# bioshield.net
KiCad netlist of a schematic drawn in EAGLE
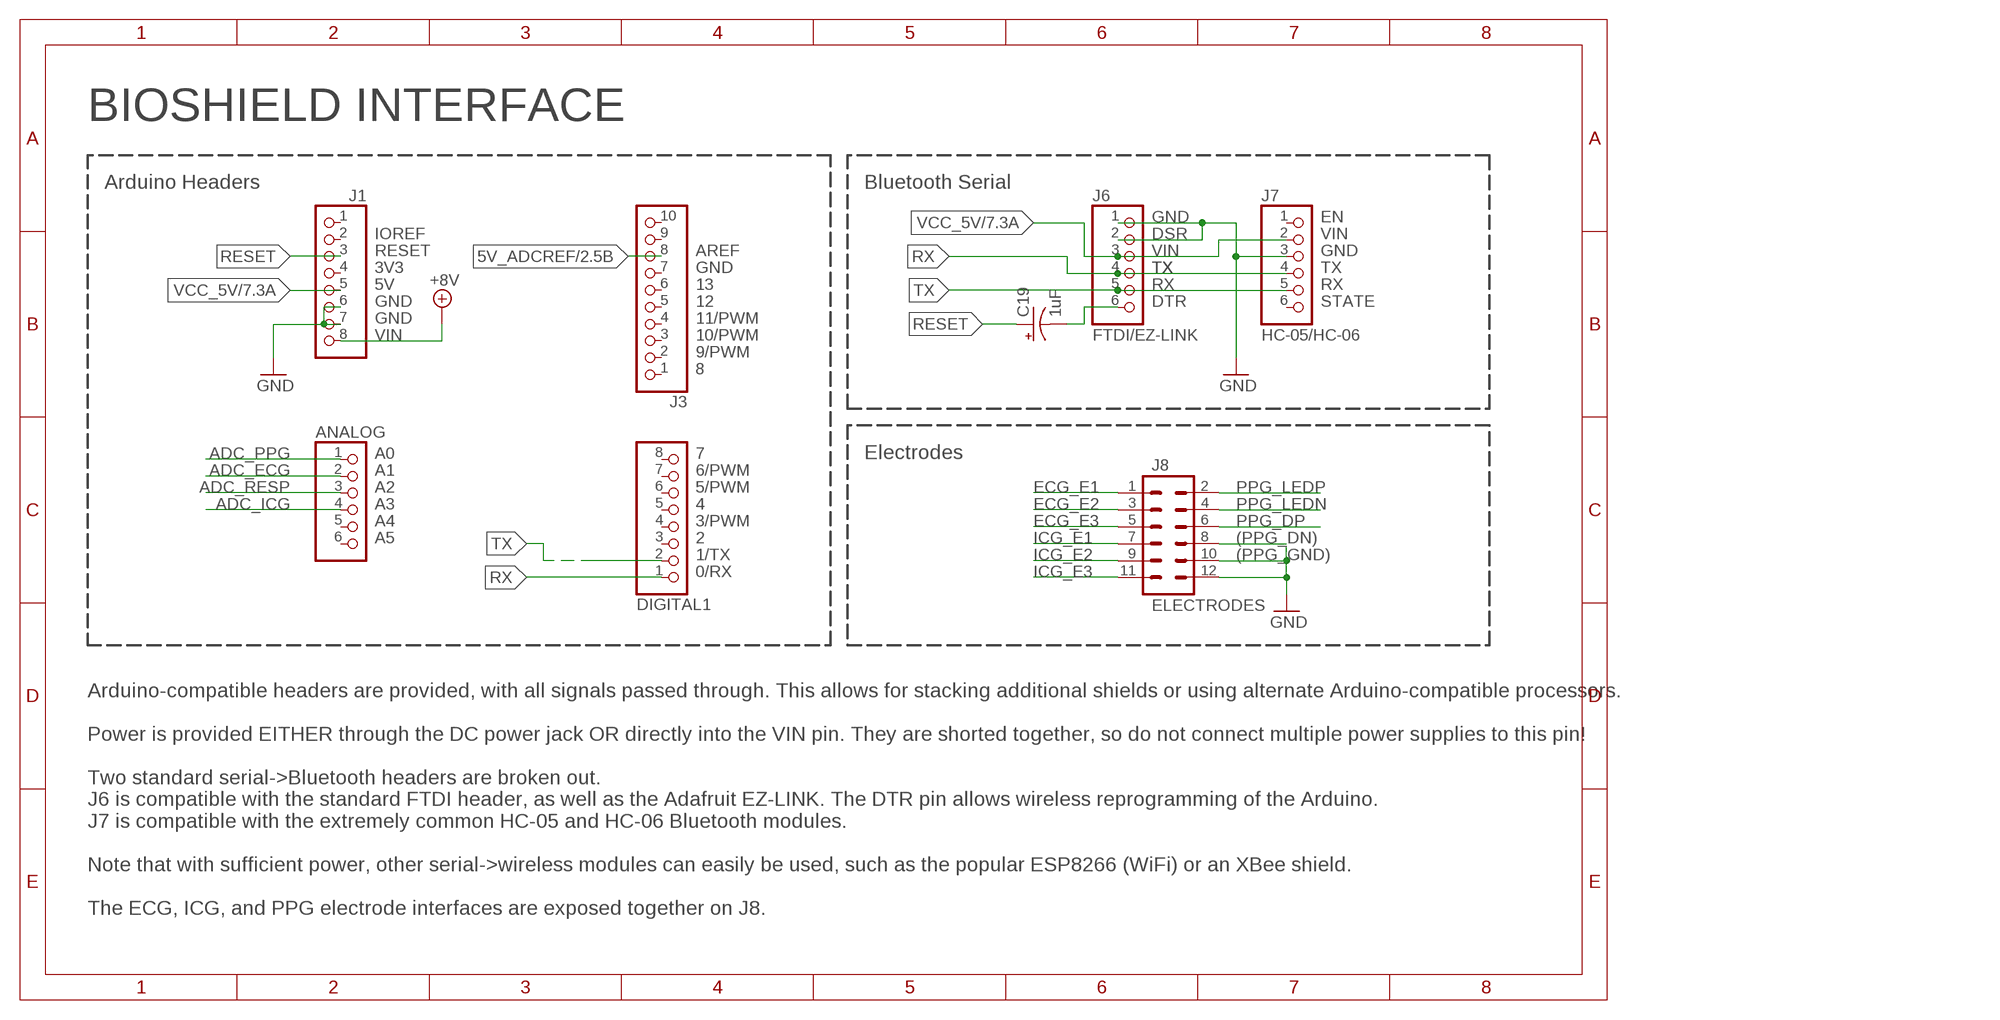
[diagram p0: schematic, sheet 1]
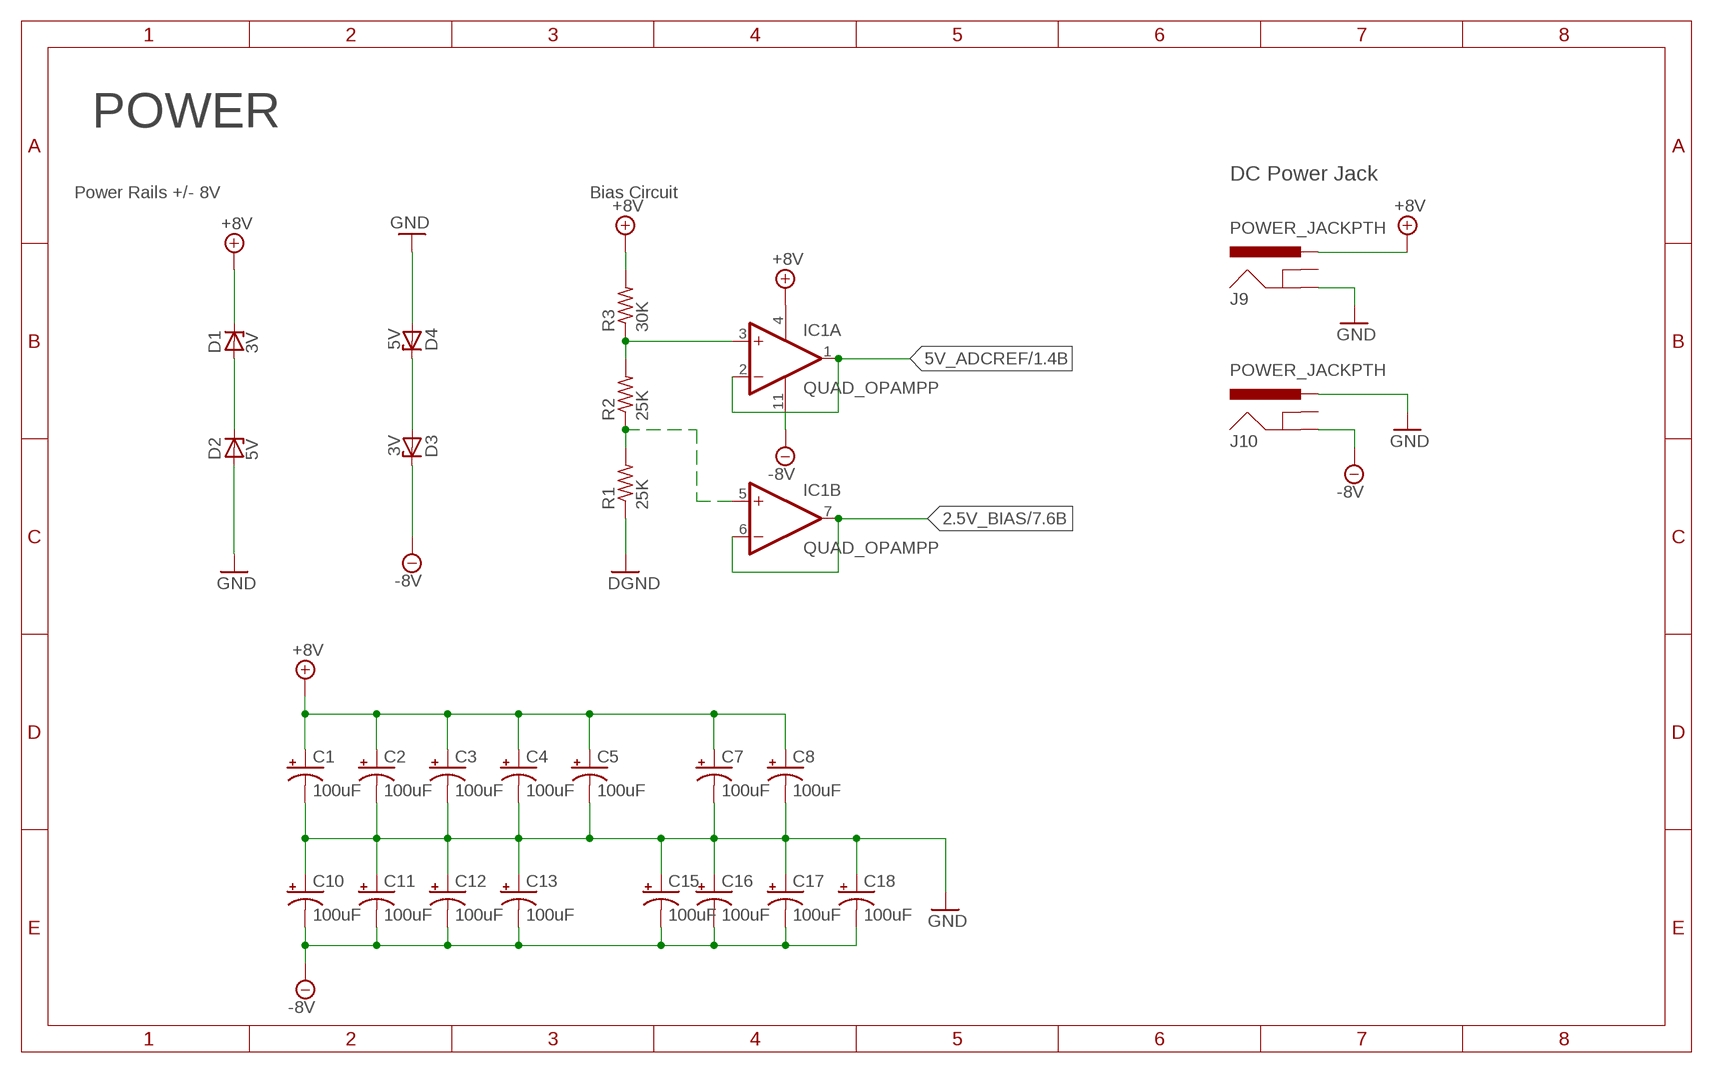
[diagram p1: schematic, sheet 2]
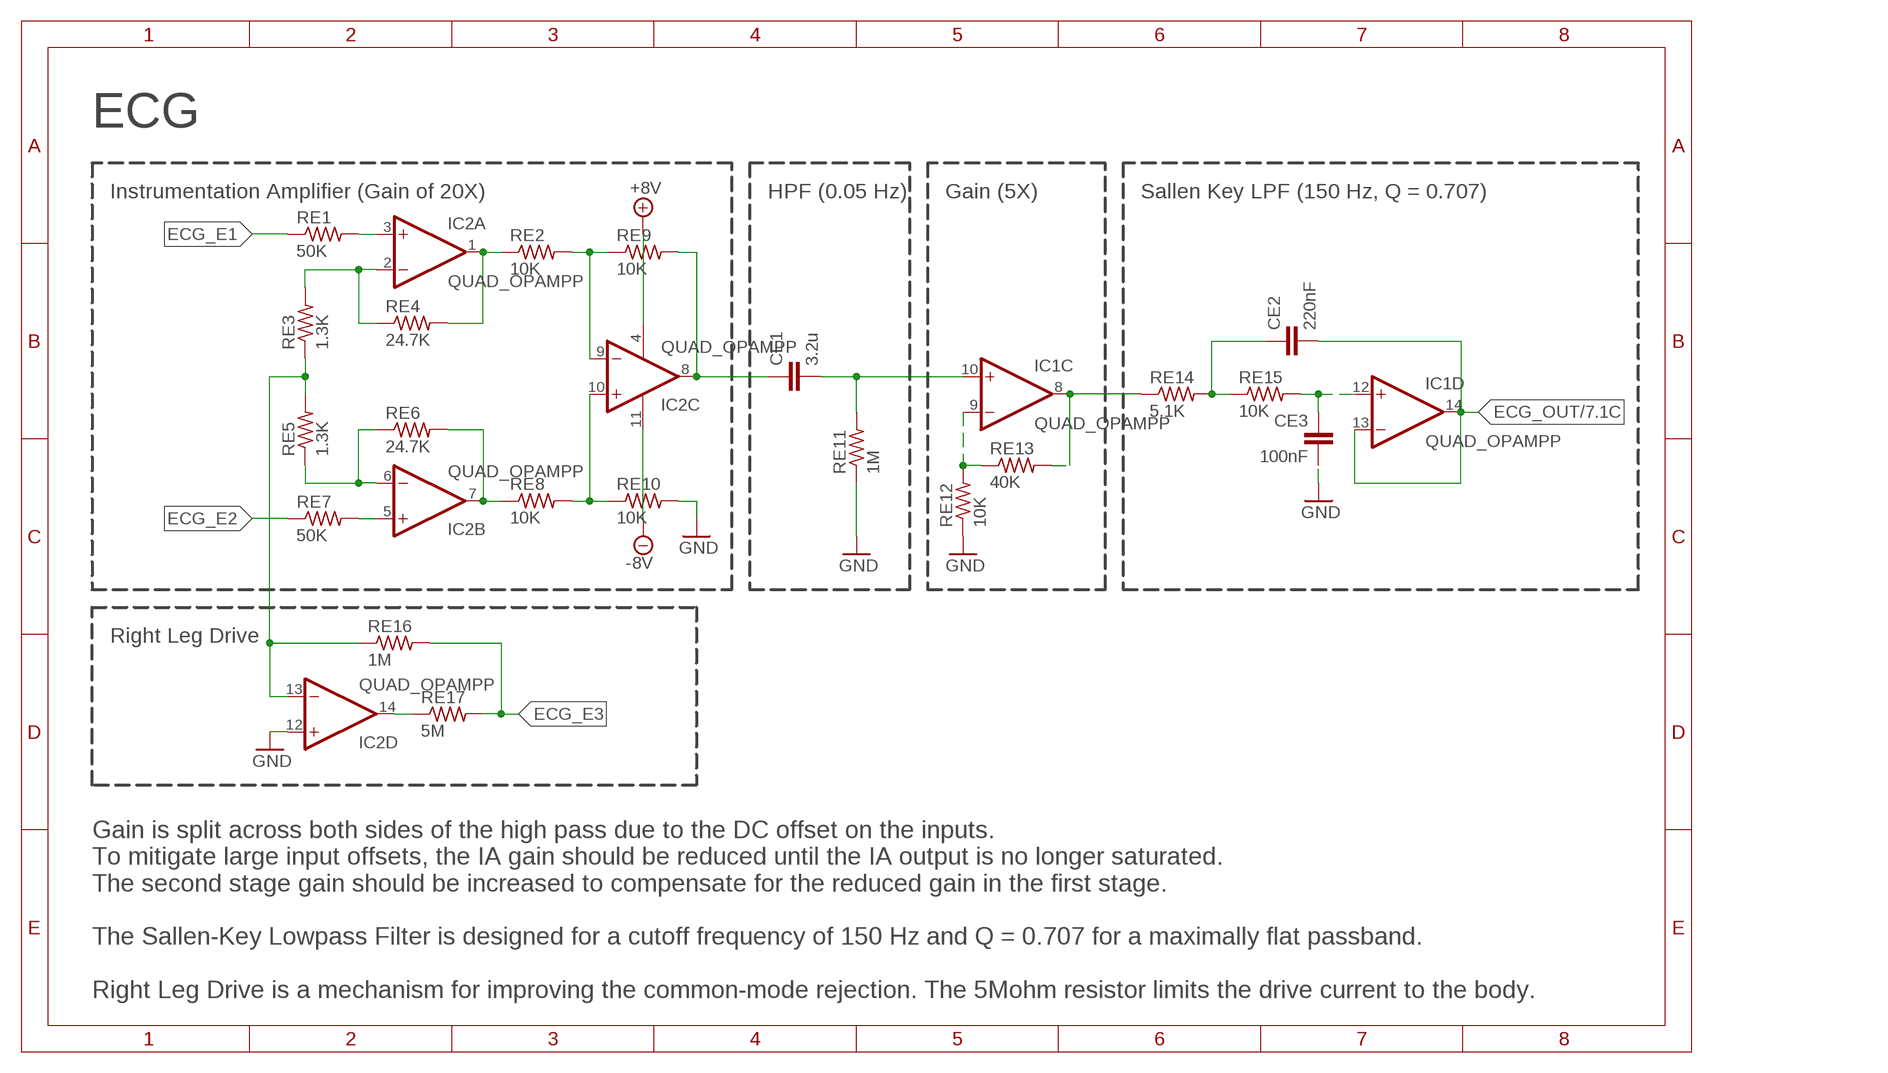
[diagram p2: schematic, sheet 3]
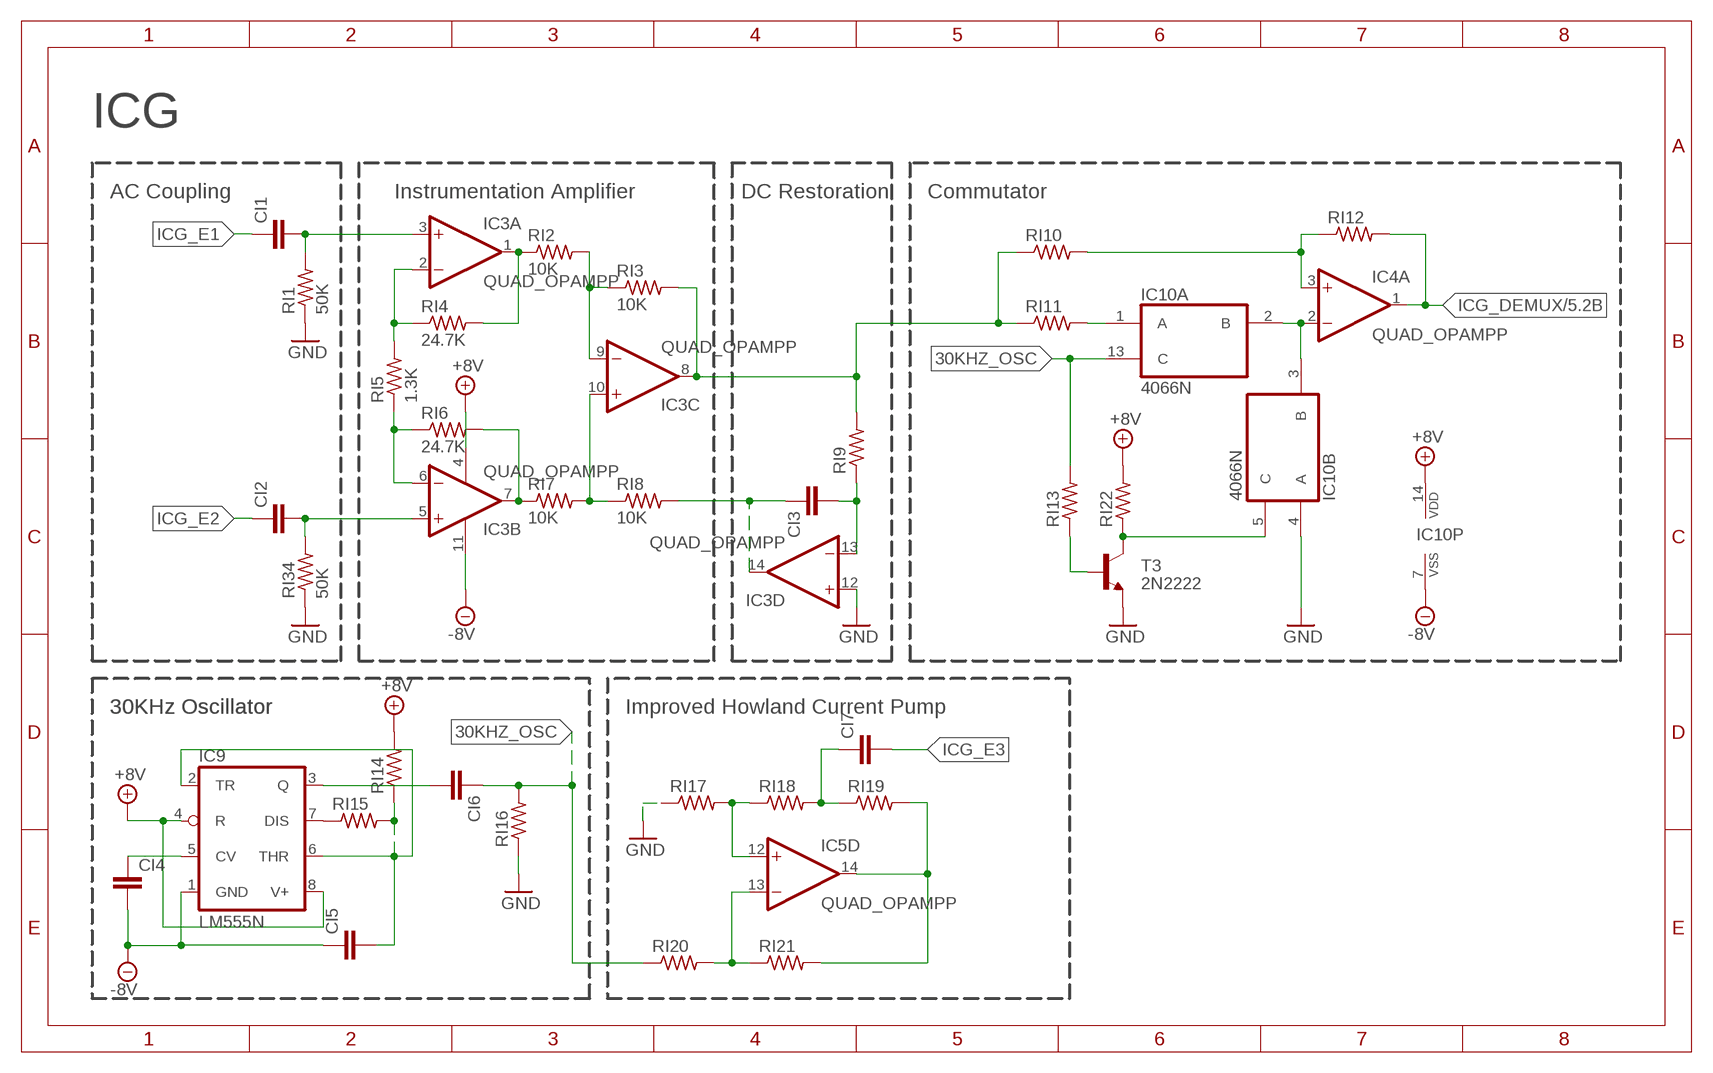
[diagram p3: schematic, sheet 4]
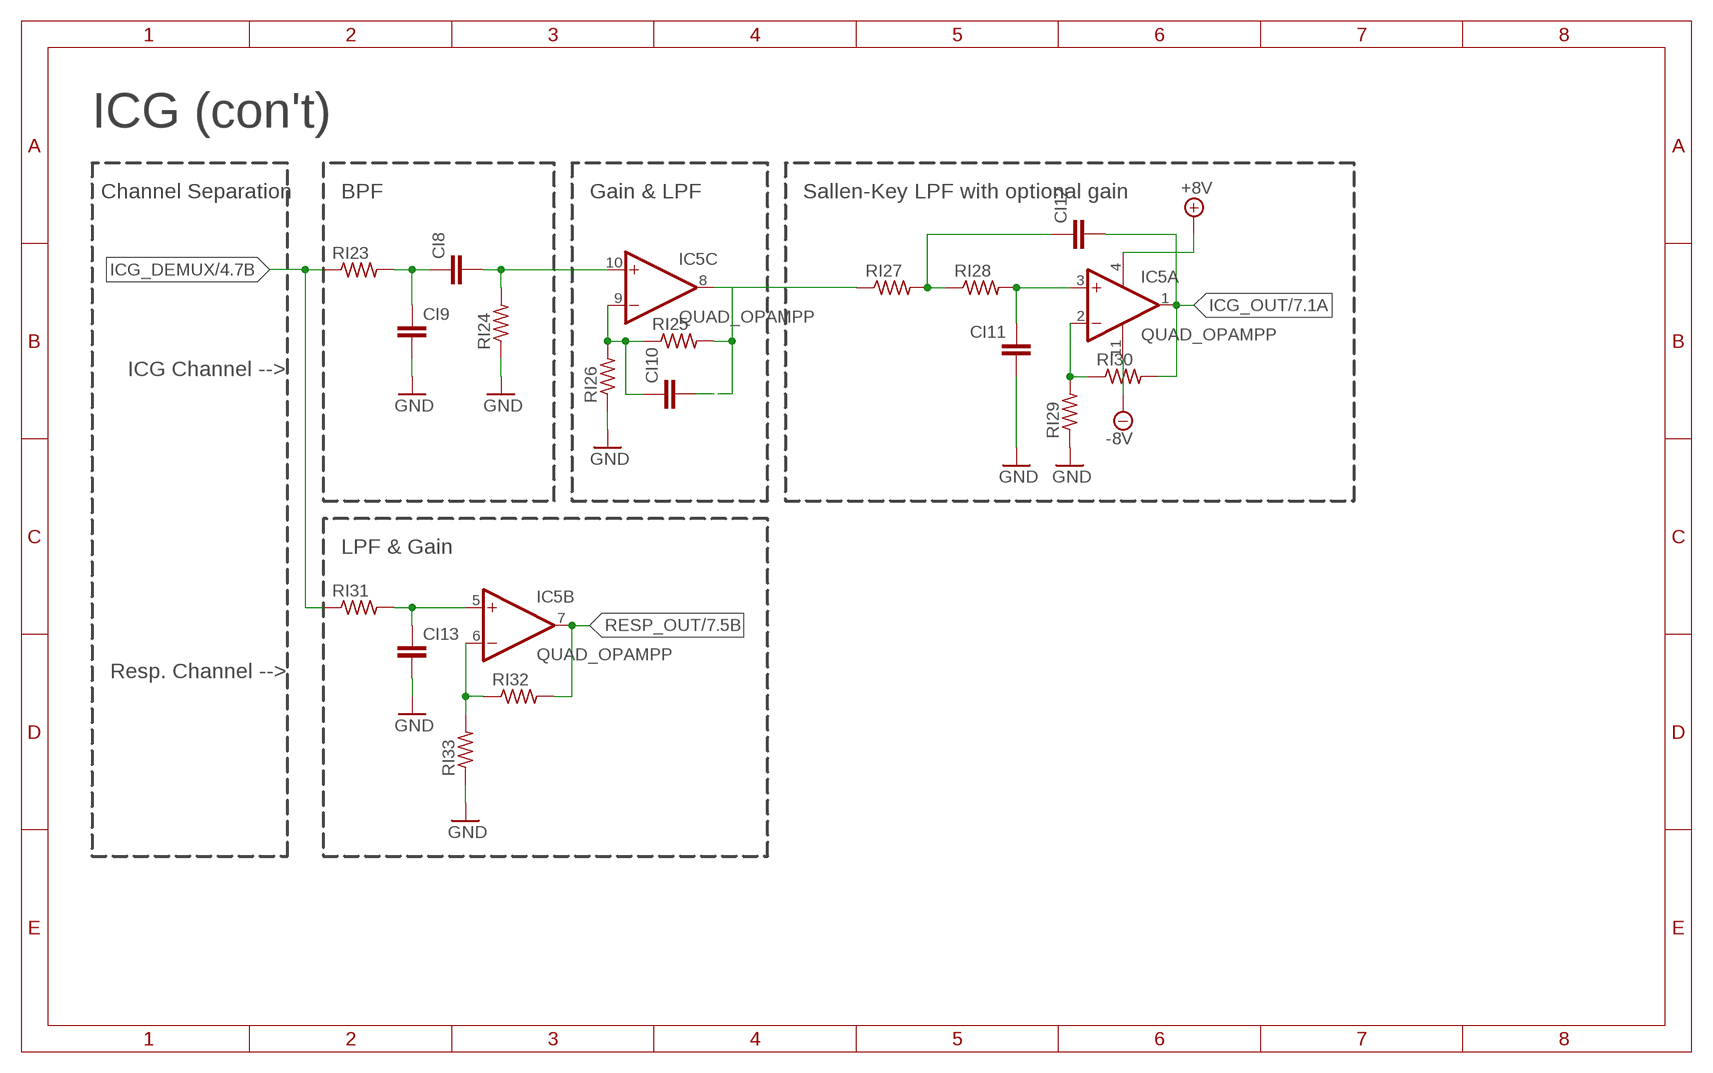
[diagram p4: schematic, sheet 5]
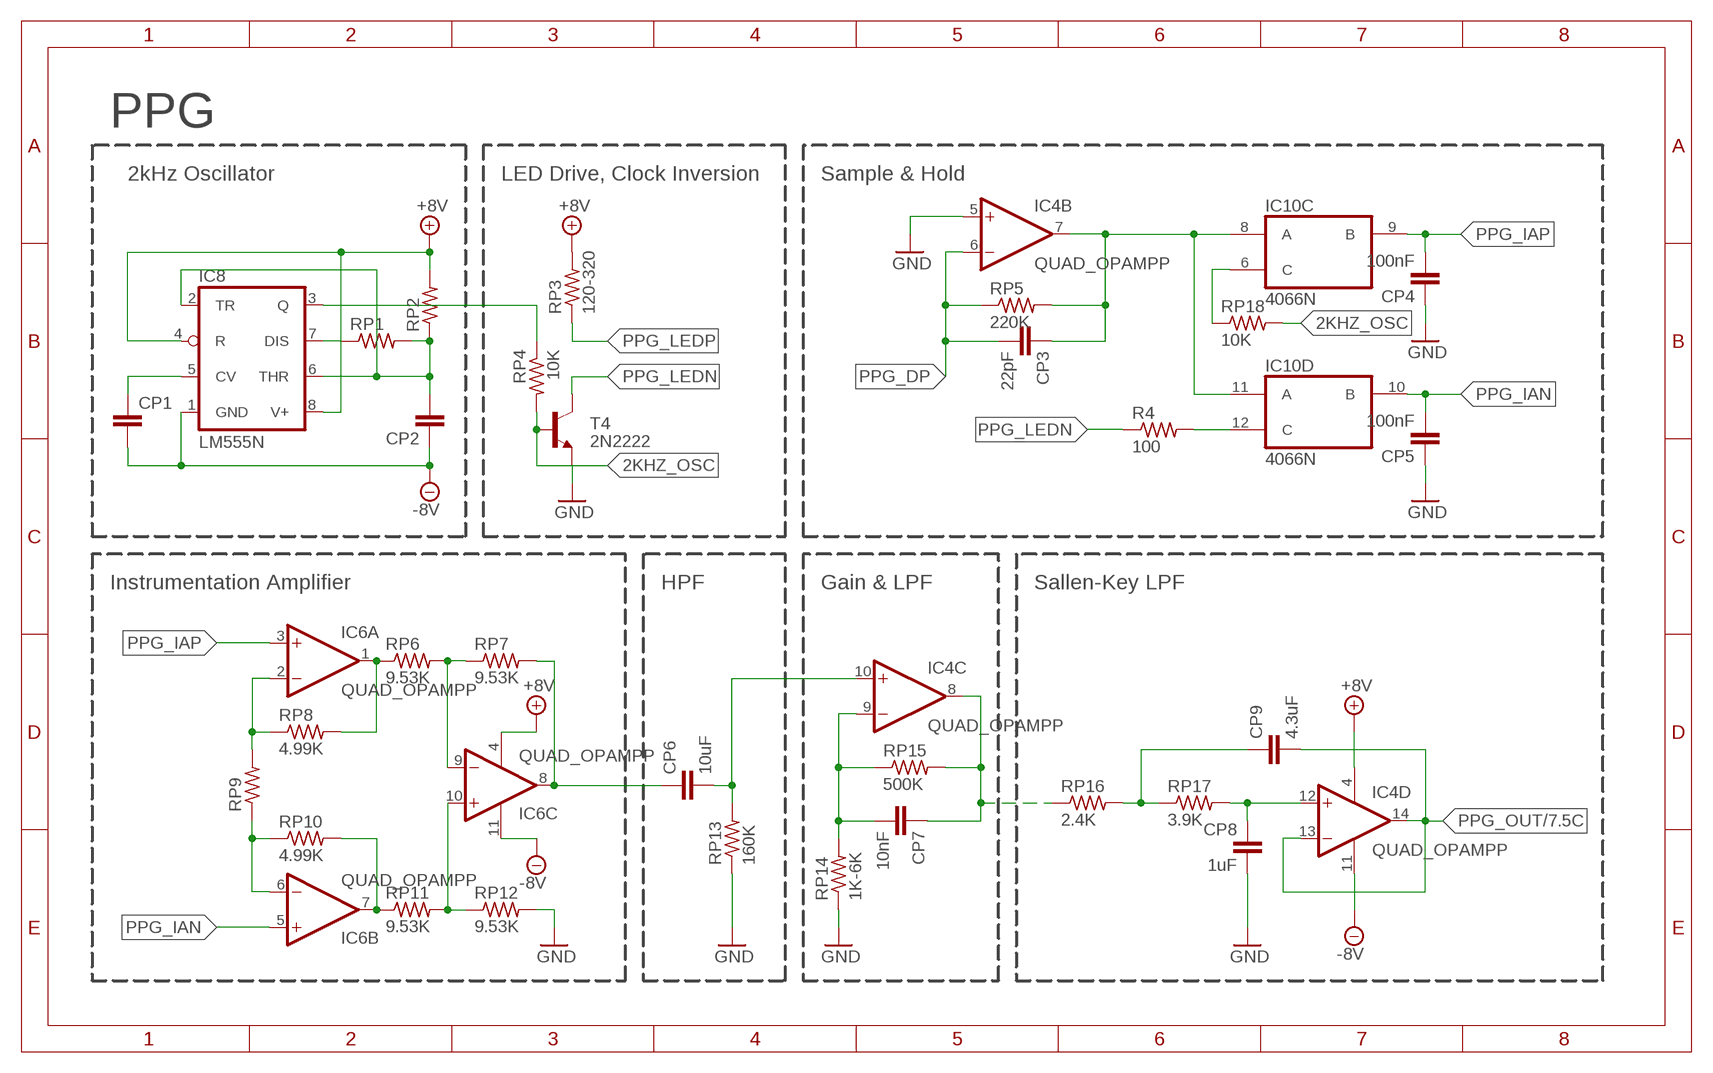
[diagram p5: schematic, sheet 6]
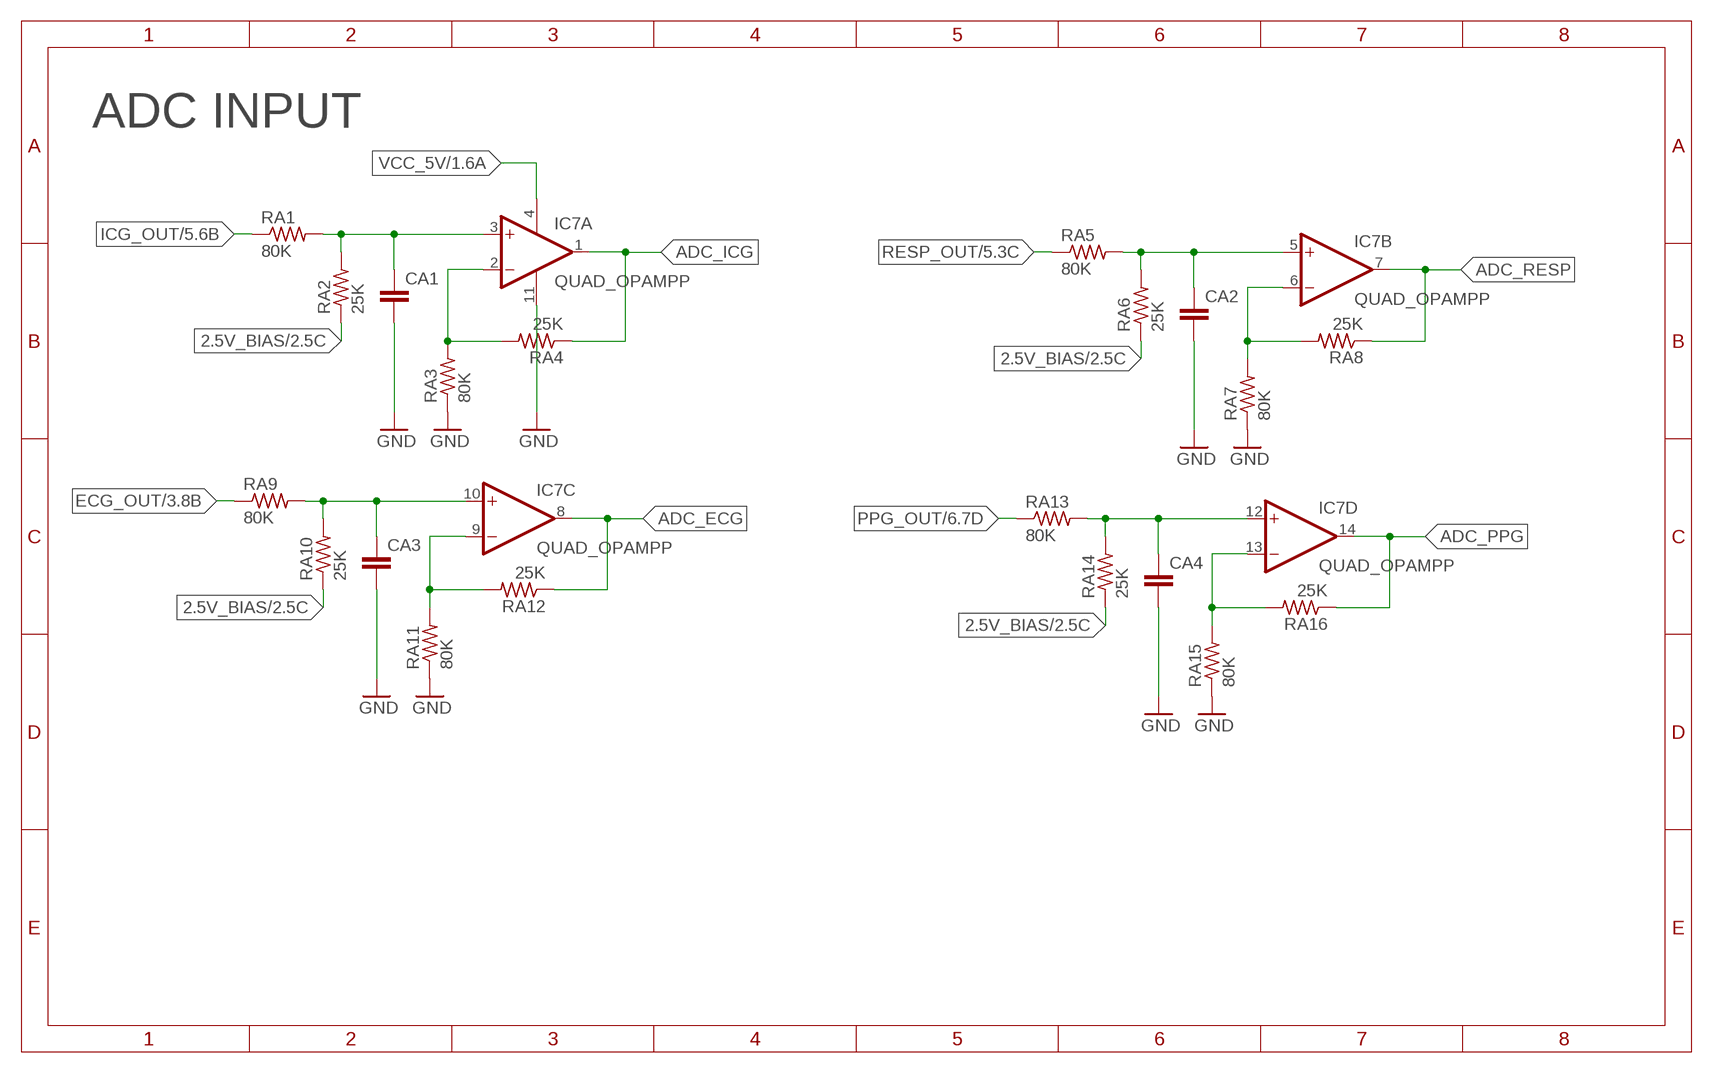
[diagram p6: schematic, sheet 7]

(export (version "E")
  (design (tool "Eeschema 10.0.6"))
  (components
    (comp (ref "CE1")
      (value "3.2u")
      (footprint "eagle-import:CAP-PTH-5MM")
      (libsource (lib "eagle-import") (part "SparkFun-Passives_CAPPTH1"))
    )
    (comp (ref "CE2")
      (value "220nF")
      (footprint "eagle-import:CAP-PTH-5MM")
      (libsource (lib "eagle-import") (part "SparkFun-Passives_CAPPTH1"))
    )
    (comp (ref "CE3")
      (value "100nF")
      (footprint "eagle-import:CAP-PTH-5MM")
      (libsource (lib "eagle-import") (part "SparkFun-Passives_CAPPTH1"))
    )
    (comp (ref "IC1")
      (value "QUAD_OPAMPP")
      (footprint "eagle-import:DIL14")
      (libsource (lib "eagle-import") (part "QUAD_OPAMPP"))
    )
    (comp (ref "IC2")
      (value "QUAD_OPAMPP")
      (footprint "eagle-import:DIL14")
      (libsource (lib "eagle-import") (part "QUAD_OPAMPP"))
    )
    (comp (ref "RE1")
      (value "50K")
      (footprint "eagle-import:0207_10")
      (libsource (lib "eagle-import") (part "R-US_0207/10"))
    )
    (comp (ref "RE2")
      (value "10K")
      (footprint "eagle-import:0207_10")
      (libsource (lib "eagle-import") (part "R-US_0207/10"))
    )
    (comp (ref "RE3")
      (value "1.3K")
      (footprint "eagle-import:0207_10")
      (libsource (lib "eagle-import") (part "R-US_0207/10"))
    )
    (comp (ref "RE4")
      (value "24.7K")
      (footprint "eagle-import:0207_10")
      (libsource (lib "eagle-import") (part "R-US_0207/10"))
    )
    (comp (ref "RE5")
      (value "1.3K")
      (footprint "eagle-import:0207_10")
      (libsource (lib "eagle-import") (part "R-US_0207/10"))
    )
    (comp (ref "RE6")
      (value "24.7K")
      (footprint "eagle-import:0207_10")
      (libsource (lib "eagle-import") (part "R-US_0207/10"))
    )
    (comp (ref "RE7")
      (value "50K")
      (footprint "eagle-import:0207_10")
      (libsource (lib "eagle-import") (part "R-US_0207/10"))
    )
    (comp (ref "RE8")
      (value "10K")
      (footprint "eagle-import:0207_10")
      (libsource (lib "eagle-import") (part "R-US_0207/10"))
    )
    (comp (ref "RE9")
      (value "10K")
      (footprint "eagle-import:0207_10")
      (libsource (lib "eagle-import") (part "R-US_0207/10"))
    )
    (comp (ref "RE10")
      (value "10K")
      (footprint "eagle-import:0207_10")
      (libsource (lib "eagle-import") (part "R-US_0207/10"))
    )
    (comp (ref "RE11")
      (value "1M")
      (footprint "eagle-import:0207_10")
      (libsource (lib "eagle-import") (part "R-US_0207/10"))
    )
    (comp (ref "RE12")
      (value "10K")
      (footprint "eagle-import:0207_10")
      (libsource (lib "eagle-import") (part "R-US_0207/10"))
    )
    (comp (ref "RE13")
      (value "40K")
      (footprint "eagle-import:0207_10")
      (libsource (lib "eagle-import") (part "R-US_0207/10"))
    )
    (comp (ref "RE14")
      (value "5.1K")
      (footprint "eagle-import:0207_10")
      (libsource (lib "eagle-import") (part "R-US_0207/10"))
    )
    (comp (ref "RE15")
      (value "10K")
      (footprint "eagle-import:0207_10")
      (libsource (lib "eagle-import") (part "R-US_0207/10"))
    )
    (comp (ref "RE16")
      (value "1M")
      (footprint "eagle-import:0207_10")
      (libsource (lib "eagle-import") (part "R-US_0207/10"))
    )
    (comp (ref "RE17")
      (value "5M")
      (footprint "eagle-import:0207_10")
      (libsource (lib "eagle-import") (part "R-US_0207/10"))
    )
    (comp (ref "CA1")
      (value "CAPPTH1")
      (footprint "eagle-import:CAP-PTH-5MM")
      (libsource (lib "eagle-import") (part "CAPPTH1"))
    )
    (comp (ref "CA2")
      (value "CAPPTH1")
      (footprint "eagle-import:CAP-PTH-5MM")
      (libsource (lib "eagle-import") (part "CAPPTH1"))
    )
    (comp (ref "CA3")
      (value "CAPPTH1")
      (footprint "eagle-import:CAP-PTH-5MM")
      (libsource (lib "eagle-import") (part "CAPPTH1"))
    )
    (comp (ref "CA4")
      (value "CAPPTH1")
      (footprint "eagle-import:CAP-PTH-5MM")
      (libsource (lib "eagle-import") (part "CAPPTH1"))
    )
    (comp (ref "IC7")
      (value "QUAD_OPAMPP")
      (footprint "eagle-import:DIL14")
      (libsource (lib "eagle-import") (part "QUAD_OPAMPP"))
    )
    (comp (ref "RA1")
      (value "80K")
      (footprint "eagle-import:0207_10")
      (libsource (lib "eagle-import") (part "R-US_0207/10"))
    )
    (comp (ref "RA2")
      (value "25K")
      (footprint "eagle-import:0207_10")
      (libsource (lib "eagle-import") (part "R-US_0207/10"))
    )
    (comp (ref "RA3")
      (value "80K")
      (footprint "eagle-import:0207_10")
      (libsource (lib "eagle-import") (part "R-US_0207/10"))
    )
    (comp (ref "RA4")
      (value "25K")
      (footprint "eagle-import:0207_10")
      (libsource (lib "eagle-import") (part "R-US_0207/10"))
    )
    (comp (ref "RA5")
      (value "80K")
      (footprint "eagle-import:0207_10")
      (libsource (lib "eagle-import") (part "R-US_0207/10"))
    )
    (comp (ref "RA6")
      (value "25K")
      (footprint "eagle-import:0207_10")
      (libsource (lib "eagle-import") (part "R-US_0207/10"))
    )
    (comp (ref "RA7")
      (value "80K")
      (footprint "eagle-import:0207_10")
      (libsource (lib "eagle-import") (part "R-US_0207/10"))
    )
    (comp (ref "RA8")
      (value "25K")
      (footprint "eagle-import:0207_10")
      (libsource (lib "eagle-import") (part "R-US_0207/10"))
    )
    (comp (ref "RA9")
      (value "80K")
      (footprint "eagle-import:0207_10")
      (libsource (lib "eagle-import") (part "R-US_0207/10"))
    )
    (comp (ref "RA10")
      (value "25K")
      (footprint "eagle-import:0207_10")
      (libsource (lib "eagle-import") (part "R-US_0207/10"))
    )
    (comp (ref "RA11")
      (value "80K")
      (footprint "eagle-import:0207_10")
      (libsource (lib "eagle-import") (part "R-US_0207/10"))
    )
    (comp (ref "RA12")
      (value "25K")
      (footprint "eagle-import:0207_10")
      (libsource (lib "eagle-import") (part "R-US_0207/10"))
    )
    (comp (ref "RA13")
      (value "80K")
      (footprint "eagle-import:0207_10")
      (libsource (lib "eagle-import") (part "R-US_0207/10"))
    )
    (comp (ref "RA14")
      (value "25K")
      (footprint "eagle-import:0207_10")
      (libsource (lib "eagle-import") (part "R-US_0207/10"))
    )
    (comp (ref "RA15")
      (value "80K")
      (footprint "eagle-import:0207_10")
      (libsource (lib "eagle-import") (part "R-US_0207/10"))
    )
    (comp (ref "RA16")
      (value "25K")
      (footprint "eagle-import:0207_10")
      (libsource (lib "eagle-import") (part "R-US_0207/10"))
    )
    (comp (ref "ANALOG")
      (value "PINHD-1X6")
      (footprint "eagle-import:1X06")
      (libsource (lib "eagle-import") (part "PINHD-1X6"))
    )
    (comp (ref "C19")
      (value "1uF")
      (footprint "eagle-import:E2-5")
      (libsource (lib "eagle-import") (part "CPOL-USE2-5"))
    )
    (comp (ref "DIGITAL1")
      (value "PINHD-1X8TH")
      (footprint "eagle-import:1X08-TH")
      (libsource (lib "eagle-import") (part "PINHD-1X8TH"))
    )
    (comp (ref "J1")
      (value "PINHD-1X8TH")
      (footprint "eagle-import:1X08-TH")
      (libsource (lib "eagle-import") (part "PINHD-1X8TH"))
    )
    (comp (ref "J3")
      (value "PINHD-1X10TH")
      (footprint "eagle-import:1X10-TH")
      (libsource (lib "eagle-import") (part "PINHD-1X10TH"))
    )
    (comp (ref "J6")
      (value "FTDI/EZ-LINK")
      (footprint "eagle-import:1X06")
      (libsource (lib "eagle-import") (part "PINHD-1X6"))
    )
    (comp (ref "J7")
      (value "HC-05/HC-06")
      (footprint "eagle-import:1X06")
      (libsource (lib "eagle-import") (part "PINHD-1X6"))
    )
    (comp (ref "J8")
      (value "ELECTRODES")
      (footprint "eagle-import:2X6")
      (libsource (lib "eagle-import") (part "M06X2PTH_FEMALE"))
    )
    (comp (ref "C1")
      (value "100uF")
      (footprint "eagle-import:CPOL-RADIAL-100UF-25V")
      (libsource (lib "eagle-import") (part "CAP_POLPTH1"))
    )
    (comp (ref "C2")
      (value "100uF")
      (footprint "eagle-import:CPOL-RADIAL-100UF-25V")
      (libsource (lib "eagle-import") (part "CAP_POLPTH1"))
    )
    (comp (ref "C3")
      (value "100uF")
      (footprint "eagle-import:CPOL-RADIAL-100UF-25V")
      (libsource (lib "eagle-import") (part "CAP_POLPTH1"))
    )
    (comp (ref "C4")
      (value "100uF")
      (footprint "eagle-import:CPOL-RADIAL-100UF-25V")
      (libsource (lib "eagle-import") (part "CAP_POLPTH1"))
    )
    (comp (ref "C5")
      (value "100uF")
      (footprint "eagle-import:CPOL-RADIAL-100UF-25V")
      (libsource (lib "eagle-import") (part "CAP_POLPTH1"))
    )
    (comp (ref "C7")
      (value "100uF")
      (footprint "eagle-import:CPOL-RADIAL-100UF-25V")
      (libsource (lib "eagle-import") (part "CAP_POLPTH1"))
    )
    (comp (ref "C8")
      (value "100uF")
      (footprint "eagle-import:CPOL-RADIAL-100UF-25V")
      (libsource (lib "eagle-import") (part "CAP_POLPTH1"))
    )
    (comp (ref "C10")
      (value "100uF")
      (footprint "eagle-import:CPOL-RADIAL-100UF-25V")
      (libsource (lib "eagle-import") (part "CAP_POLPTH1"))
    )
    (comp (ref "C11")
      (value "100uF")
      (footprint "eagle-import:CPOL-RADIAL-100UF-25V")
      (libsource (lib "eagle-import") (part "CAP_POLPTH1"))
    )
    (comp (ref "C12")
      (value "100uF")
      (footprint "eagle-import:CPOL-RADIAL-100UF-25V")
      (libsource (lib "eagle-import") (part "CAP_POLPTH1"))
    )
    (comp (ref "C13")
      (value "100uF")
      (footprint "eagle-import:CPOL-RADIAL-100UF-25V")
      (libsource (lib "eagle-import") (part "CAP_POLPTH1"))
    )
    (comp (ref "C15")
      (value "100uF")
      (footprint "eagle-import:CPOL-RADIAL-100UF-25V")
      (libsource (lib "eagle-import") (part "CAP_POLPTH1"))
    )
    (comp (ref "C16")
      (value "100uF")
      (footprint "eagle-import:CPOL-RADIAL-100UF-25V")
      (libsource (lib "eagle-import") (part "CAP_POLPTH1"))
    )
    (comp (ref "C17")
      (value "100uF")
      (footprint "eagle-import:CPOL-RADIAL-100UF-25V")
      (libsource (lib "eagle-import") (part "CAP_POLPTH1"))
    )
    (comp (ref "C18")
      (value "100uF")
      (footprint "eagle-import:CPOL-RADIAL-100UF-25V")
      (libsource (lib "eagle-import") (part "CAP_POLPTH1"))
    )
    (comp (ref "D1")
      (value "3V")
      (footprint "eagle-import:ZDIO-10")
      (libsource (lib "eagle-import") (part "ZENER-DIODEZD-10"))
    )
    (comp (ref "D2")
      (value "5V")
      (footprint "eagle-import:ZDIO-10")
      (libsource (lib "eagle-import") (part "ZENER-DIODEZD-10"))
    )
    (comp (ref "D3")
      (value "3V")
      (footprint "eagle-import:ZDIO-10")
      (libsource (lib "eagle-import") (part "ZENER-DIODEZD-10"))
    )
    (comp (ref "D4")
      (value "5V")
      (footprint "eagle-import:ZDIO-10")
      (libsource (lib "eagle-import") (part "ZENER-DIODEZD-10"))
    )
    (comp (ref "J9")
      (value "POWER_JACKPTH")
      (footprint "eagle-import:POWER_JACK_PTH")
      (libsource (lib "eagle-import") (part "POWER_JACKPTH"))
    )
    (comp (ref "J10")
      (value "POWER_JACKPTH")
      (footprint "eagle-import:POWER_JACK_PTH")
      (libsource (lib "eagle-import") (part "POWER_JACKPTH"))
    )
    (comp (ref "R1")
      (value "25K")
      (footprint "eagle-import:0207_10")
      (libsource (lib "eagle-import") (part "R-US_0207/10"))
    )
    (comp (ref "R2")
      (value "25K")
      (footprint "eagle-import:0207_10")
      (libsource (lib "eagle-import") (part "R-US_0207/10"))
    )
    (comp (ref "R3")
      (value "30K")
      (footprint "eagle-import:0207_10")
      (libsource (lib "eagle-import") (part "R-US_0207/10"))
    )
    (comp (ref "CP1")
      (value "CAPPTH1")
      (footprint "eagle-import:CAP-PTH-5MM")
      (libsource (lib "eagle-import") (part "CAPPTH1"))
    )
    (comp (ref "CP2")
      (value "CAPPTH1")
      (footprint "eagle-import:CAP-PTH-5MM")
      (libsource (lib "eagle-import") (part "CAPPTH1"))
    )
    (comp (ref "CP3")
      (value "22pF")
      (footprint "eagle-import:CAP-PTH-5MM")
      (libsource (lib "eagle-import") (part "SparkFun-Passives_CAPPTH1"))
    )
    (comp (ref "CP4")
      (value "100nF")
      (footprint "eagle-import:CAP-PTH-5MM")
      (libsource (lib "eagle-import") (part "SparkFun-Passives_CAPPTH1"))
    )
    (comp (ref "CP5")
      (value "100nF")
      (footprint "eagle-import:CAP-PTH-5MM")
      (libsource (lib "eagle-import") (part "SparkFun-Passives_CAPPTH1"))
    )
    (comp (ref "CP6")
      (value "10uF")
      (footprint "eagle-import:CAP-PTH-5MM")
      (libsource (lib "eagle-import") (part "SparkFun-Passives_CAPPTH1"))
    )
    (comp (ref "CP7")
      (value "10nF")
      (footprint "eagle-import:CAP-PTH-5MM")
      (libsource (lib "eagle-import") (part "SparkFun-Passives_CAPPTH1"))
    )
    (comp (ref "CP8")
      (value "1uF")
      (footprint "eagle-import:CAP-PTH-5MM")
      (libsource (lib "eagle-import") (part "SparkFun-Passives_CAPPTH1"))
    )
    (comp (ref "CP9")
      (value "4.3uF")
      (footprint "eagle-import:CAP-PTH-5MM")
      (libsource (lib "eagle-import") (part "SparkFun-Passives_CAPPTH1"))
    )
    (comp (ref "IC4")
      (value "QUAD_OPAMPP")
      (footprint "eagle-import:DIL14")
      (libsource (lib "eagle-import") (part "QUAD_OPAMPP"))
    )
    (comp (ref "IC6")
      (value "QUAD_OPAMPP")
      (footprint "eagle-import:DIL14")
      (libsource (lib "eagle-import") (part "QUAD_OPAMPP"))
    )
    (comp (ref "IC8")
      (value "LM555N")
      (footprint "eagle-import:DIL08")
      (libsource (lib "eagle-import") (part "555NLM"))
    )
    (comp (ref "IC10")
      (value "4066N")
      (footprint "eagle-import:DIL14")
      (libsource (lib "eagle-import") (part "4066N"))
    )
    (comp (ref "R4")
      (value "100")
      (footprint "eagle-import:0207_10")
      (libsource (lib "eagle-import") (part "R-US_0207/10"))
    )
    (comp (ref "RP1")
      (value "R-US_0207/10")
      (footprint "eagle-import:0207_10")
      (libsource (lib "eagle-import") (part "R-US_0207/10"))
    )
    (comp (ref "RP2")
      (value "R-US_0207/10")
      (footprint "eagle-import:0207_10")
      (libsource (lib "eagle-import") (part "R-US_0207/10"))
    )
    (comp (ref "RP3")
      (value "120-320")
      (footprint "eagle-import:0207_10")
      (libsource (lib "eagle-import") (part "R-US_0207/10"))
    )
    (comp (ref "RP4")
      (value "10K")
      (footprint "eagle-import:0207_10")
      (libsource (lib "eagle-import") (part "R-US_0207/10"))
    )
    (comp (ref "RP5")
      (value "220K")
      (footprint "eagle-import:0207_10")
      (libsource (lib "eagle-import") (part "R-US_0207/10"))
    )
    (comp (ref "RP6")
      (value "9.53K")
      (footprint "eagle-import:0207_10")
      (libsource (lib "eagle-import") (part "R-US_0207/10"))
    )
    (comp (ref "RP7")
      (value "9.53K")
      (footprint "eagle-import:0207_10")
      (libsource (lib "eagle-import") (part "R-US_0207/10"))
    )
    (comp (ref "RP8")
      (value "4.99K")
      (footprint "eagle-import:0207_10")
      (libsource (lib "eagle-import") (part "R-US_0207/10"))
    )
    (comp (ref "RP9")
      (value "R-US_0207/10")
      (footprint "eagle-import:0207_10")
      (libsource (lib "eagle-import") (part "R-US_0207/10"))
    )
    (comp (ref "RP10")
      (value "4.99K")
      (footprint "eagle-import:0207_10")
      (libsource (lib "eagle-import") (part "R-US_0207/10"))
    )
    (comp (ref "RP11")
      (value "9.53K")
      (footprint "eagle-import:0207_10")
      (libsource (lib "eagle-import") (part "R-US_0207/10"))
    )
    (comp (ref "RP12")
      (value "9.53K")
      (footprint "eagle-import:0207_10")
      (libsource (lib "eagle-import") (part "R-US_0207/10"))
    )
    (comp (ref "RP13")
      (value "160K")
      (footprint "eagle-import:0207_10")
      (libsource (lib "eagle-import") (part "R-US_0207/10"))
    )
    (comp (ref "RP14")
      (value "1K-6K")
      (footprint "eagle-import:0207_10")
      (libsource (lib "eagle-import") (part "R-US_0207/10"))
    )
    (comp (ref "RP15")
      (value "500K")
      (footprint "eagle-import:0207_10")
      (libsource (lib "eagle-import") (part "R-US_0207/10"))
    )
    (comp (ref "RP16")
      (value "2.4K")
      (footprint "eagle-import:0207_10")
      (libsource (lib "eagle-import") (part "R-US_0207/10"))
    )
    (comp (ref "RP17")
      (value "3.9K")
      (footprint "eagle-import:0207_10")
      (libsource (lib "eagle-import") (part "R-US_0207/10"))
    )
    (comp (ref "RP18")
      (value "10K")
      (footprint "eagle-import:0207_10")
      (libsource (lib "eagle-import") (part "R-US_0207/10"))
    )
    (comp (ref "T4")
      (value "2N2222")
      (footprint "eagle-import:TO92-EBC-OVAL")
      (libsource (lib "eagle-import") (part "2N2222"))
    )
    (comp (ref "CI8")
      (value "CAPPTH1")
      (footprint "eagle-import:CAP-PTH-5MM")
      (libsource (lib "eagle-import") (part "CAPPTH1"))
    )
    (comp (ref "CI9")
      (value "CAPPTH1")
      (footprint "eagle-import:CAP-PTH-5MM")
      (libsource (lib "eagle-import") (part "CAPPTH1"))
    )
    (comp (ref "CI10")
      (value "CAPPTH1")
      (footprint "eagle-import:CAP-PTH-5MM")
      (libsource (lib "eagle-import") (part "CAPPTH1"))
    )
    (comp (ref "CI11")
      (value "CAPPTH1")
      (footprint "eagle-import:CAP-PTH-5MM")
      (libsource (lib "eagle-import") (part "CAPPTH1"))
    )
    (comp (ref "CI12")
      (value "CAPPTH1")
      (footprint "eagle-import:CAP-PTH-5MM")
      (libsource (lib "eagle-import") (part "CAPPTH1"))
    )
    (comp (ref "CI13")
      (value "CAPPTH1")
      (footprint "eagle-import:CAP-PTH-5MM")
      (libsource (lib "eagle-import") (part "CAPPTH1"))
    )
    (comp (ref "IC5")
      (value "QUAD_OPAMPP")
      (footprint "eagle-import:DIL14")
      (libsource (lib "eagle-import") (part "QUAD_OPAMPP"))
    )
    (comp (ref "RI23")
      (value "R-US_0207/10")
      (footprint "eagle-import:0207_10")
      (libsource (lib "eagle-import") (part "R-US_0207/10"))
    )
    (comp (ref "RI24")
      (value "R-US_0207/10")
      (footprint "eagle-import:0207_10")
      (libsource (lib "eagle-import") (part "R-US_0207/10"))
    )
    (comp (ref "RI25")
      (value "R-US_0207/10")
      (footprint "eagle-import:0207_10")
      (libsource (lib "eagle-import") (part "R-US_0207/10"))
    )
    (comp (ref "RI26")
      (value "R-US_0207/10")
      (footprint "eagle-import:0207_10")
      (libsource (lib "eagle-import") (part "R-US_0207/10"))
    )
    (comp (ref "RI27")
      (value "R-US_0207/10")
      (footprint "eagle-import:0207_10")
      (libsource (lib "eagle-import") (part "R-US_0207/10"))
    )
    (comp (ref "RI28")
      (value "R-US_0207/10")
      (footprint "eagle-import:0207_10")
      (libsource (lib "eagle-import") (part "R-US_0207/10"))
    )
    (comp (ref "RI29")
      (value "R-US_0207/10")
      (footprint "eagle-import:0207_10")
      (libsource (lib "eagle-import") (part "R-US_0207/10"))
    )
    (comp (ref "RI30")
      (value "R-US_0207/10")
      (footprint "eagle-import:0207_10")
      (libsource (lib "eagle-import") (part "R-US_0207/10"))
    )
    (comp (ref "RI31")
      (value "R-US_0207/10")
      (footprint "eagle-import:0207_10")
      (libsource (lib "eagle-import") (part "R-US_0207/10"))
    )
    (comp (ref "RI32")
      (value "R-US_0207/10")
      (footprint "eagle-import:0207_10")
      (libsource (lib "eagle-import") (part "R-US_0207/10"))
    )
    (comp (ref "RI33")
      (value "R-US_0207/10")
      (footprint "eagle-import:0207_10")
      (libsource (lib "eagle-import") (part "R-US_0207/10"))
    )
    (comp (ref "CI1")
      (value "CAPPTH1")
      (footprint "eagle-import:CAP-PTH-5MM")
      (libsource (lib "eagle-import") (part "CAPPTH1"))
    )
    (comp (ref "CI2")
      (value "CAPPTH1")
      (footprint "eagle-import:CAP-PTH-5MM")
      (libsource (lib "eagle-import") (part "CAPPTH1"))
    )
    (comp (ref "CI3")
      (value "CAPPTH1")
      (footprint "eagle-import:CAP-PTH-5MM")
      (libsource (lib "eagle-import") (part "CAPPTH1"))
    )
    (comp (ref "CI4")
      (value "CAPPTH1")
      (footprint "eagle-import:CAP-PTH-5MM")
      (libsource (lib "eagle-import") (part "CAPPTH1"))
    )
    (comp (ref "CI5")
      (value "CAPPTH1")
      (footprint "eagle-import:CAP-PTH-5MM")
      (libsource (lib "eagle-import") (part "CAPPTH1"))
    )
    (comp (ref "CI6")
      (value "CAPPTH1")
      (footprint "eagle-import:CAP-PTH-5MM")
      (libsource (lib "eagle-import") (part "CAPPTH1"))
    )
    (comp (ref "CI7")
      (value "CAPPTH1")
      (footprint "eagle-import:CAP-PTH-5MM")
      (libsource (lib "eagle-import") (part "CAPPTH1"))
    )
    (comp (ref "IC3")
      (value "QUAD_OPAMPP")
      (footprint "eagle-import:DIL14")
      (libsource (lib "eagle-import") (part "QUAD_OPAMPP"))
    )
    (comp (ref "IC9")
      (value "LM555N")
      (footprint "eagle-import:DIL08")
      (libsource (lib "eagle-import") (part "555NLM"))
    )
    (comp (ref "RI1")
      (value "50K")
      (footprint "eagle-import:0207_10")
      (libsource (lib "eagle-import") (part "R-US_0207/10"))
    )
    (comp (ref "RI2")
      (value "10K")
      (footprint "eagle-import:0207_10")
      (libsource (lib "eagle-import") (part "R-US_0207/10"))
    )
    (comp (ref "RI3")
      (value "10K")
      (footprint "eagle-import:0207_10")
      (libsource (lib "eagle-import") (part "R-US_0207/10"))
    )
    (comp (ref "RI4")
      (value "24.7K")
      (footprint "eagle-import:0207_10")
      (libsource (lib "eagle-import") (part "R-US_0207/10"))
    )
    (comp (ref "RI5")
      (value "1.3K")
      (footprint "eagle-import:0207_10")
      (libsource (lib "eagle-import") (part "R-US_0207/10"))
    )
    (comp (ref "RI6")
      (value "24.7K")
      (footprint "eagle-import:0207_10")
      (libsource (lib "eagle-import") (part "R-US_0207/10"))
    )
    (comp (ref "RI7")
      (value "10K")
      (footprint "eagle-import:0207_10")
      (libsource (lib "eagle-import") (part "R-US_0207/10"))
    )
    (comp (ref "RI8")
      (value "10K")
      (footprint "eagle-import:0207_10")
      (libsource (lib "eagle-import") (part "R-US_0207/10"))
    )
    (comp (ref "RI9")
      (value "R-US_0207/10")
      (footprint "eagle-import:0207_10")
      (libsource (lib "eagle-import") (part "R-US_0207/10"))
    )
    (comp (ref "RI10")
      (value "R-US_0207/10")
      (footprint "eagle-import:0207_10")
      (libsource (lib "eagle-import") (part "R-US_0207/10"))
    )
    (comp (ref "RI11")
      (value "R-US_0207/10")
      (footprint "eagle-import:0207_10")
      (libsource (lib "eagle-import") (part "R-US_0207/10"))
    )
    (comp (ref "RI12")
      (value "R-US_0207/10")
      (footprint "eagle-import:0207_10")
      (libsource (lib "eagle-import") (part "R-US_0207/10"))
    )
    (comp (ref "RI13")
      (value "R-US_0207/10")
      (footprint "eagle-import:0207_10")
      (libsource (lib "eagle-import") (part "R-US_0207/10"))
    )
    (comp (ref "RI14")
      (value "R-US_0207/10")
      (footprint "eagle-import:0207_10")
      (libsource (lib "eagle-import") (part "R-US_0207/10"))
    )
    (comp (ref "RI15")
      (value "R-US_0207/10")
      (footprint "eagle-import:0207_10")
      (libsource (lib "eagle-import") (part "R-US_0207/10"))
    )
    (comp (ref "RI16")
      (value "R-US_0207/10")
      (footprint "eagle-import:0207_10")
      (libsource (lib "eagle-import") (part "R-US_0207/10"))
    )
    (comp (ref "RI17")
      (value "R-US_0207/10")
      (footprint "eagle-import:0207_10")
      (libsource (lib "eagle-import") (part "R-US_0207/10"))
    )
    (comp (ref "RI18")
      (value "R-US_0207/10")
      (footprint "eagle-import:0207_10")
      (libsource (lib "eagle-import") (part "R-US_0207/10"))
    )
    (comp (ref "RI19")
      (value "R-US_0207/10")
      (footprint "eagle-import:0207_10")
      (libsource (lib "eagle-import") (part "R-US_0207/10"))
    )
    (comp (ref "RI20")
      (value "R-US_0207/10")
      (footprint "eagle-import:0207_10")
      (libsource (lib "eagle-import") (part "R-US_0207/10"))
    )
    (comp (ref "RI21")
      (value "R-US_0207/10")
      (footprint "eagle-import:0207_10")
      (libsource (lib "eagle-import") (part "R-US_0207/10"))
    )
    (comp (ref "RI22")
      (value "R-US_0207/10")
      (footprint "eagle-import:0207_10")
      (libsource (lib "eagle-import") (part "R-US_0207/10"))
    )
    (comp (ref "RI34")
      (value "50K")
      (footprint "eagle-import:0207_10")
      (libsource (lib "eagle-import") (part "R-US_0207/10"))
    )
    (comp (ref "T3")
      (value "2N2222")
      (footprint "eagle-import:TO92-EBC-OVAL")
      (libsource (lib "eagle-import") (part "2N2222"))
    )
  )
  (nets
    (net (code "1") (name "+8V") (class "Default")
      (node (ref "C1") (pin "1") (pinfunction "+_1") (pintype "passive"))
      (node (ref "C2") (pin "1") (pinfunction "+_1") (pintype "passive"))
      (node (ref "C3") (pin "1") (pinfunction "+_1") (pintype "passive"))
      (node (ref "C4") (pin "1") (pinfunction "+_1") (pintype "passive"))
      (node (ref "C5") (pin "1") (pinfunction "+_1") (pintype "passive"))
      (node (ref "C7") (pin "1") (pinfunction "+_1") (pintype "passive"))
      (node (ref "C8") (pin "1") (pinfunction "+_1") (pintype "passive"))
      (node (ref "D1") (pin "C") (pinfunction "C_C") (pintype "passive"))
      (node (ref "IC1") (pin "4") (pinfunction "V+_4") (pintype "power_in"))
      (node (ref "IC10") (pin "14") (pinfunction "VDD_14") (pintype "power_in"))
      (node (ref "IC2") (pin "4") (pinfunction "V+_4") (pintype "power_in"))
      (node (ref "IC3") (pin "4") (pinfunction "V+_4") (pintype "power_in"))
      (node (ref "IC4") (pin "4") (pinfunction "V+_4") (pintype "power_in"))
      (node (ref "IC5") (pin "4") (pinfunction "V+_4") (pintype "power_in"))
      (node (ref "IC6") (pin "4") (pinfunction "V+_4") (pintype "power_in"))
      (node (ref "IC8") (pin "4") (pinfunction "R_4") (pintype "input"))
      (node (ref "IC8") (pin "8") (pinfunction "V+_8") (pintype "power_in"))
      (node (ref "IC9") (pin "4") (pinfunction "R_4") (pintype "input"))
      (node (ref "IC9") (pin "8") (pinfunction "V+_8") (pintype "power_in"))
      (node (ref "J1") (pin "8") (pinfunction "8_8") (pintype "passive"))
      (node (ref "J9") (pin "PWR") (pinfunction "PWR_PWR") (pintype "bidirectional"))
      (node (ref "R3") (pin "2") (pinfunction "2_2") (pintype "passive"))
      (node (ref "RI14") (pin "2") (pinfunction "2_2") (pintype "passive"))
      (node (ref "RI22") (pin "2") (pinfunction "2_2") (pintype "passive"))
      (node (ref "RP2") (pin "2") (pinfunction "2_2") (pintype "passive"))
      (node (ref "RP3") (pin "2") (pinfunction "2_2") (pintype "passive"))
    )
    (net (code "2") (name "-8V") (class "Default")
      (node (ref "C10") (pin "2") (pinfunction "-_2") (pintype "passive"))
      (node (ref "C11") (pin "2") (pinfunction "-_2") (pintype "passive"))
      (node (ref "C12") (pin "2") (pinfunction "-_2") (pintype "passive"))
      (node (ref "C13") (pin "2") (pinfunction "-_2") (pintype "passive"))
      (node (ref "C15") (pin "2") (pinfunction "-_2") (pintype "passive"))
      (node (ref "C16") (pin "2") (pinfunction "-_2") (pintype "passive"))
      (node (ref "C17") (pin "2") (pinfunction "-_2") (pintype "passive"))
      (node (ref "C18") (pin "2") (pinfunction "-_2") (pintype "passive"))
      (node (ref "CI4") (pin "2") (pinfunction "2_2") (pintype "passive"))
      (node (ref "CI5") (pin "1") (pinfunction "1_1") (pintype "passive"))
      (node (ref "CP1") (pin "2") (pinfunction "2_2") (pintype "passive"))
      (node (ref "CP2") (pin "1") (pinfunction "1_1") (pintype "passive"))
      (node (ref "D3") (pin "C") (pinfunction "C_C") (pintype "passive"))
      (node (ref "IC1") (pin "11") (pinfunction "V-_11") (pintype "power_in"))
      (node (ref "IC10") (pin "7") (pinfunction "VSS_7") (pintype "power_in"))
      (node (ref "IC2") (pin "11") (pinfunction "V-_11") (pintype "power_in"))
      (node (ref "IC3") (pin "11") (pinfunction "V-_11") (pintype "power_in"))
      (node (ref "IC4") (pin "11") (pinfunction "V-_11") (pintype "power_in"))
      (node (ref "IC5") (pin "11") (pinfunction "V-_11") (pintype "power_in"))
      (node (ref "IC6") (pin "11") (pinfunction "V-_11") (pintype "power_in"))
      (node (ref "IC8") (pin "1") (pinfunction "GND_1") (pintype "power_in"))
      (node (ref "IC9") (pin "1") (pinfunction "GND_1") (pintype "power_in"))
      (node (ref "J10") (pin "GND") (pinfunction "GND_GND") (pintype "bidirectional"))
    )
    (net (code "3") (name "2.5V_BIAS") (class "Default")
      (node (ref "IC1") (pin "6") (pinfunction "-IN_6") (pintype "input"))
      (node (ref "IC1") (pin "7") (pinfunction "OUT_7") (pintype "output"))
      (node (ref "RA10") (pin "1") (pinfunction "1_1") (pintype "passive"))
      (node (ref "RA14") (pin "1") (pinfunction "1_1") (pintype "passive"))
      (node (ref "RA2") (pin "1") (pinfunction "1_1") (pintype "passive"))
      (node (ref "RA6") (pin "1") (pinfunction "1_1") (pintype "passive"))
    )
    (net (code "4") (name "2KHZ_OSC") (class "Default")
      (node (ref "RP18") (pin "2") (pinfunction "2_2") (pintype "passive"))
      (node (ref "RP4") (pin "2") (pinfunction "2_2") (pintype "passive"))
      (node (ref "T4") (pin "B") (pinfunction "B_B") (pintype "passive"))
    )
    (net (code "5") (name "5V_ADCREF") (class "Default")
      (node (ref "IC1") (pin "1") (pinfunction "OUT_1") (pintype "output"))
      (node (ref "IC1") (pin "2") (pinfunction "-IN_2") (pintype "input"))
      (node (ref "J3") (pin "8") (pinfunction "8_8") (pintype "passive"))
    )
    (net (code "6") (name "30KHZ_OSC") (class "Default")
      (node (ref "CI6") (pin "1") (pinfunction "1_1") (pintype "passive"))
      (node (ref "IC10") (pin "13") (pinfunction "C_13") (pintype "input"))
      (node (ref "RI13") (pin "2") (pinfunction "2_2") (pintype "passive"))
      (node (ref "RI16") (pin "2") (pinfunction "2_2") (pintype "passive"))
      (node (ref "RI20") (pin "1") (pinfunction "1_1") (pintype "passive"))
    )
    (net (code "7") (name "ADC_ECG") (class "Default")
      (node (ref "ANALOG") (pin "2") (pinfunction "2_2") (pintype "passive"))
      (node (ref "IC7") (pin "8") (pinfunction "OUT_8") (pintype "output"))
      (node (ref "RA12") (pin "1") (pinfunction "1_1") (pintype "passive"))
    )
    (net (code "8") (name "ADC_ICG") (class "Default")
      (node (ref "ANALOG") (pin "4") (pinfunction "4_4") (pintype "passive"))
      (node (ref "IC7") (pin "1") (pinfunction "OUT_1") (pintype "output"))
      (node (ref "RA4") (pin "1") (pinfunction "1_1") (pintype "passive"))
    )
    (net (code "9") (name "ADC_PPG") (class "Default")
      (node (ref "ANALOG") (pin "1") (pinfunction "1_1") (pintype "passive"))
      (node (ref "IC7") (pin "14") (pinfunction "OUT_14") (pintype "output"))
      (node (ref "RA16") (pin "1") (pinfunction "1_1") (pintype "passive"))
    )
    (net (code "10") (name "ADC_RESP") (class "Default")
      (node (ref "ANALOG") (pin "3") (pinfunction "3_3") (pintype "passive"))
      (node (ref "IC7") (pin "7") (pinfunction "OUT_7") (pintype "output"))
      (node (ref "RA8") (pin "1") (pinfunction "1_1") (pintype "passive"))
    )
    (net (code "11") (name "ECG_E1") (class "Default")
      (node (ref "J8") (pin "1") (pinfunction "1_1") (pintype "passive"))
      (node (ref "RE1") (pin "1") (pinfunction "1_1") (pintype "passive"))
    )
    (net (code "12") (name "ECG_E2") (class "Default")
      (node (ref "J8") (pin "3") (pinfunction "3_3") (pintype "passive"))
      (node (ref "RE7") (pin "1") (pinfunction "1_1") (pintype "passive"))
    )
    (net (code "13") (name "ECG_E3") (class "Default")
      (node (ref "J8") (pin "5") (pinfunction "5_5") (pintype "passive"))
      (node (ref "RE16") (pin "2") (pinfunction "2_2") (pintype "passive"))
      (node (ref "RE17") (pin "2") (pinfunction "2_2") (pintype "passive"))
    )
    (net (code "14") (name "ECG_OUT") (class "Default")
      (node (ref "CE2") (pin "2") (pinfunction "2_2") (pintype "passive"))
      (node (ref "IC1") (pin "13") (pinfunction "-IN_13") (pintype "input"))
      (node (ref "IC1") (pin "14") (pinfunction "OUT_14") (pintype "output"))
      (node (ref "RA9") (pin "1") (pinfunction "1_1") (pintype "passive"))
    )
    (net (code "15") (name "GND") (class "Default")
      (node (ref "C1") (pin "2") (pinfunction "-_2") (pintype "passive"))
      (node (ref "C10") (pin "1") (pinfunction "+_1") (pintype "passive"))
      (node (ref "C11") (pin "1") (pinfunction "+_1") (pintype "passive"))
      (node (ref "C12") (pin "1") (pinfunction "+_1") (pintype "passive"))
      (node (ref "C13") (pin "1") (pinfunction "+_1") (pintype "passive"))
      (node (ref "C15") (pin "1") (pinfunction "+_1") (pintype "passive"))
      (node (ref "C16") (pin "1") (pinfunction "+_1") (pintype "passive"))
      (node (ref "C17") (pin "1") (pinfunction "+_1") (pintype "passive"))
      (node (ref "C18") (pin "1") (pinfunction "+_1") (pintype "passive"))
      (node (ref "C2") (pin "2") (pinfunction "-_2") (pintype "passive"))
      (node (ref "C3") (pin "2") (pinfunction "-_2") (pintype "passive"))
      (node (ref "C4") (pin "2") (pinfunction "-_2") (pintype "passive"))
      (node (ref "C5") (pin "2") (pinfunction "-_2") (pintype "passive"))
      (node (ref "C7") (pin "2") (pinfunction "-_2") (pintype "passive"))
      (node (ref "C8") (pin "2") (pinfunction "-_2") (pintype "passive"))
      (node (ref "CA1") (pin "2") (pinfunction "2_2") (pintype "passive"))
      (node (ref "CA2") (pin "2") (pinfunction "2_2") (pintype "passive"))
      (node (ref "CA3") (pin "2") (pinfunction "2_2") (pintype "passive"))
      (node (ref "CA4") (pin "2") (pinfunction "2_2") (pintype "passive"))
      (node (ref "CE3") (pin "2") (pinfunction "2_2") (pintype "passive"))
      (node (ref "CI11") (pin "2") (pinfunction "2_2") (pintype "passive"))
      (node (ref "CI13") (pin "2") (pinfunction "2_2") (pintype "passive"))
      (node (ref "CI9") (pin "2") (pinfunction "2_2") (pintype "passive"))
      (node (ref "CP4") (pin "1") (pinfunction "1_1") (pintype "passive"))
      (node (ref "CP5") (pin "1") (pinfunction "1_1") (pintype "passive"))
      (node (ref "CP8") (pin "2") (pinfunction "2_2") (pintype "passive"))
      (node (ref "D2") (pin "A") (pinfunction "A_A") (pintype "passive"))
      (node (ref "D4") (pin "A") (pinfunction "A_A") (pintype "passive"))
      (node (ref "IC10") (pin "4") (pinfunction "A_4") (pintype "tri_state"))
      (node (ref "IC2") (pin "12") (pinfunction "+IN_12") (pintype "input"))
      (node (ref "IC3") (pin "12") (pinfunction "+IN_12") (pintype "input"))
      (node (ref "IC4") (pin "5") (pinfunction "+IN_5") (pintype "input"))
      (node (ref "IC7") (pin "11") (pinfunction "V-_11") (pintype "power_in"))
      (node (ref "J1") (pin "6") (pinfunction "6_6") (pintype "passive"))
      (node (ref "J1") (pin "7") (pinfunction "7_7") (pintype "passive"))
      (node (ref "J10") (pin "PWR") (pinfunction "PWR_PWR") (pintype "bidirectional"))
      (node (ref "J6") (pin "1") (pinfunction "1_1") (pintype "passive"))
      (node (ref "J6") (pin "2") (pinfunction "2_2") (pintype "passive"))
      (node (ref "J7") (pin "3") (pinfunction "3_3") (pintype "passive"))
      (node (ref "J8") (pin "10") (pinfunction "10_10") (pintype "passive"))
      (node (ref "J8") (pin "12") (pinfunction "12_12") (pintype "passive"))
      (node (ref "J8") (pin "8") (pinfunction "8_8") (pintype "passive"))
      (node (ref "J9") (pin "GND") (pinfunction "GND_GND") (pintype "bidirectional"))
      (node (ref "R1") (pin "1") (pinfunction "1_1") (pintype "passive"))
      (node (ref "RA11") (pin "1") (pinfunction "1_1") (pintype "passive"))
      (node (ref "RA15") (pin "1") (pinfunction "1_1") (pintype "passive"))
      (node (ref "RA3") (pin "1") (pinfunction "1_1") (pintype "passive"))
      (node (ref "RA7") (pin "1") (pinfunction "1_1") (pintype "passive"))
      (node (ref "RE10") (pin "2") (pinfunction "2_2") (pintype "passive"))
      (node (ref "RE11") (pin "1") (pinfunction "1_1") (pintype "passive"))
      (node (ref "RE12") (pin "1") (pinfunction "1_1") (pintype "passive"))
      (node (ref "RI1") (pin "1") (pinfunction "1_1") (pintype "passive"))
      (node (ref "RI16") (pin "1") (pinfunction "1_1") (pintype "passive"))
      (node (ref "RI17") (pin "1") (pinfunction "1_1") (pintype "passive"))
      (node (ref "RI24") (pin "1") (pinfunction "1_1") (pintype "passive"))
      (node (ref "RI26") (pin "1") (pinfunction "1_1") (pintype "passive"))
      (node (ref "RI29") (pin "1") (pinfunction "1_1") (pintype "passive"))
      (node (ref "RI33") (pin "1") (pinfunction "1_1") (pintype "passive"))
      (node (ref "RI34") (pin "1") (pinfunction "1_1") (pintype "passive"))
      (node (ref "RP12") (pin "2") (pinfunction "2_2") (pintype "passive"))
      (node (ref "RP13") (pin "1") (pinfunction "1_1") (pintype "passive"))
      (node (ref "RP14") (pin "1") (pinfunction "1_1") (pintype "passive"))
      (node (ref "T3") (pin "E") (pinfunction "E_E") (pintype "passive"))
      (node (ref "T4") (pin "E") (pinfunction "E_E") (pintype "passive"))
    )
    (net (code "16") (name "ICG_DEMUX") (class "Default")
      (node (ref "IC4") (pin "1") (pinfunction "OUT_1") (pintype "output"))
      (node (ref "RI12") (pin "2") (pinfunction "2_2") (pintype "passive"))
      (node (ref "RI23") (pin "1") (pinfunction "1_1") (pintype "passive"))
      (node (ref "RI31") (pin "1") (pinfunction "1_1") (pintype "passive"))
    )
    (net (code "17") (name "ICG_E1") (class "Default")
      (node (ref "CI1") (pin "1") (pinfunction "1_1") (pintype "passive"))
      (node (ref "J8") (pin "7") (pinfunction "7_7") (pintype "passive"))
    )
    (net (code "18") (name "ICG_E2") (class "Default")
      (node (ref "CI2") (pin "1") (pinfunction "1_1") (pintype "passive"))
      (node (ref "J8") (pin "9") (pinfunction "9_9") (pintype "passive"))
    )
    (net (code "19") (name "ICG_E3") (class "Default")
      (node (ref "CI7") (pin "2") (pinfunction "2_2") (pintype "passive"))
      (node (ref "J8") (pin "11") (pinfunction "11_11") (pintype "passive"))
    )
    (net (code "20") (name "ICG_OUT") (class "Default")
      (node (ref "CI12") (pin "2") (pinfunction "2_2") (pintype "passive"))
      (node (ref "IC5") (pin "1") (pinfunction "OUT_1") (pintype "output"))
      (node (ref "RA1") (pin "1") (pinfunction "1_1") (pintype "passive"))
      (node (ref "RI30") (pin "2") (pinfunction "2_2") (pintype "passive"))
    )
    (net (code "21") (name "Net-(C19-Pad-)") (class "Default")
      (node (ref "C19") (pin "-") (pinfunction "-_-") (pintype "passive"))
      (node (ref "J6") (pin "6") (pinfunction "6_6") (pintype "passive"))
    )
    (net (code "22") (name "Net-(CE2-Pad1)") (class "Default")
      (node (ref "CE2") (pin "1") (pinfunction "1_1") (pintype "passive"))
      (node (ref "RE14") (pin "2") (pinfunction "2_2") (pintype "passive"))
      (node (ref "RE15") (pin "1") (pinfunction "1_1") (pintype "passive"))
    )
    (net (code "23") (name "Net-(CI7-Pad1)") (class "Default")
      (node (ref "CI7") (pin "1") (pinfunction "1_1") (pintype "passive"))
      (node (ref "RI18") (pin "2") (pinfunction "2_2") (pintype "passive"))
      (node (ref "RI19") (pin "1") (pinfunction "1_1") (pintype "passive"))
    )
    (net (code "24") (name "Net-(CI8-Pad1)") (class "Default")
      (node (ref "CI8") (pin "1") (pinfunction "1_1") (pintype "passive"))
      (node (ref "CI9") (pin "1") (pinfunction "1_1") (pintype "passive"))
      (node (ref "RI23") (pin "2") (pinfunction "2_2") (pintype "passive"))
    )
    (net (code "25") (name "Net-(CI12-Pad1)") (class "Default")
      (node (ref "CI12") (pin "1") (pinfunction "1_1") (pintype "passive"))
      (node (ref "RI27") (pin "2") (pinfunction "2_2") (pintype "passive"))
      (node (ref "RI28") (pin "1") (pinfunction "1_1") (pintype "passive"))
    )
    (net (code "26") (name "Net-(CP9-Pad1)") (class "Default")
      (node (ref "CP9") (pin "1") (pinfunction "1_1") (pintype "passive"))
      (node (ref "RP16") (pin "2") (pinfunction "2_2") (pintype "passive"))
      (node (ref "RP17") (pin "1") (pinfunction "1_1") (pintype "passive"))
    )
    (net (code "27") (name "Net-(D1-PadA)") (class "Default")
      (node (ref "D1") (pin "A") (pinfunction "A_A") (pintype "passive"))
      (node (ref "D2") (pin "C") (pinfunction "C_C") (pintype "passive"))
    )
    (net (code "28") (name "Net-(D3-PadA)") (class "Default")
      (node (ref "D3") (pin "A") (pinfunction "A_A") (pintype "passive"))
      (node (ref "D4") (pin "C") (pinfunction "C_C") (pintype "passive"))
    )
    (net (code "29") (name "Net-(IC1A-+IN)") (class "Default")
      (node (ref "IC1") (pin "3") (pinfunction "+IN_3") (pintype "input"))
      (node (ref "R2") (pin "2") (pinfunction "2_2") (pintype "passive"))
      (node (ref "R3") (pin "1") (pinfunction "1_1") (pintype "passive"))
    )
    (net (code "30") (name "Net-(IC1B-+IN)") (class "Default")
      (node (ref "IC1") (pin "5") (pinfunction "+IN_5") (pintype "input"))
      (node (ref "R1") (pin "2") (pinfunction "2_2") (pintype "passive"))
      (node (ref "R2") (pin "1") (pinfunction "1_1") (pintype "passive"))
    )
    (net (code "31") (name "Net-(IC1C-+IN)") (class "Default")
      (node (ref "CE1") (pin "2") (pinfunction "2_2") (pintype "passive"))
      (node (ref "IC1") (pin "10") (pinfunction "+IN_10") (pintype "input"))
      (node (ref "RE11") (pin "2") (pinfunction "2_2") (pintype "passive"))
    )
    (net (code "32") (name "Net-(IC1C--IN)") (class "Default")
      (node (ref "IC1") (pin "9") (pinfunction "-IN_9") (pintype "input"))
      (node (ref "RE12") (pin "2") (pinfunction "2_2") (pintype "passive"))
      (node (ref "RE13") (pin "1") (pinfunction "1_1") (pintype "passive"))
    )
    (net (code "33") (name "Net-(IC1C-OUT)") (class "Default")
      (node (ref "IC1") (pin "8") (pinfunction "OUT_8") (pintype "output"))
      (node (ref "RE13") (pin "2") (pinfunction "2_2") (pintype "passive"))
      (node (ref "RE14") (pin "1") (pinfunction "1_1") (pintype "passive"))
    )
    (net (code "34") (name "Net-(IC1D-+IN)") (class "Default")
      (node (ref "CE3") (pin "1") (pinfunction "1_1") (pintype "passive"))
      (node (ref "IC1") (pin "12") (pinfunction "+IN_12") (pintype "input"))
      (node (ref "RE15") (pin "2") (pinfunction "2_2") (pintype "passive"))
    )
    (net (code "35") (name "Net-(IC2A-+IN)") (class "Default")
      (node (ref "IC2") (pin "3") (pinfunction "+IN_3") (pintype "input"))
      (node (ref "RE1") (pin "2") (pinfunction "2_2") (pintype "passive"))
    )
    (net (code "36") (name "Net-(IC2A--IN)") (class "Default")
      (node (ref "IC2") (pin "2") (pinfunction "-IN_2") (pintype "input"))
      (node (ref "RE3") (pin "2") (pinfunction "2_2") (pintype "passive"))
      (node (ref "RE4") (pin "1") (pinfunction "1_1") (pintype "passive"))
    )
    (net (code "37") (name "Net-(IC2A-OUT)") (class "Default")
      (node (ref "IC2") (pin "1") (pinfunction "OUT_1") (pintype "output"))
      (node (ref "RE2") (pin "1") (pinfunction "1_1") (pintype "passive"))
      (node (ref "RE4") (pin "2") (pinfunction "2_2") (pintype "passive"))
    )
    (net (code "38") (name "Net-(IC2B-+IN)") (class "Default")
      (node (ref "IC2") (pin "5") (pinfunction "+IN_5") (pintype "input"))
      (node (ref "RE7") (pin "2") (pinfunction "2_2") (pintype "passive"))
    )
    (net (code "39") (name "Net-(IC2B--IN)") (class "Default")
      (node (ref "IC2") (pin "6") (pinfunction "-IN_6") (pintype "input"))
      (node (ref "RE5") (pin "1") (pinfunction "1_1") (pintype "passive"))
      (node (ref "RE6") (pin "1") (pinfunction "1_1") (pintype "passive"))
    )
    (net (code "40") (name "Net-(IC2B-OUT)") (class "Default")
      (node (ref "IC2") (pin "7") (pinfunction "OUT_7") (pintype "output"))
      (node (ref "RE6") (pin "2") (pinfunction "2_2") (pintype "passive"))
      (node (ref "RE8") (pin "1") (pinfunction "1_1") (pintype "passive"))
    )
    (net (code "41") (name "Net-(IC2C-+IN)") (class "Default")
      (node (ref "IC2") (pin "10") (pinfunction "+IN_10") (pintype "input"))
      (node (ref "RE10") (pin "1") (pinfunction "1_1") (pintype "passive"))
      (node (ref "RE8") (pin "2") (pinfunction "2_2") (pintype "passive"))
    )
    (net (code "42") (name "Net-(IC2C--IN)") (class "Default")
      (node (ref "IC2") (pin "9") (pinfunction "-IN_9") (pintype "input"))
      (node (ref "RE2") (pin "2") (pinfunction "2_2") (pintype "passive"))
      (node (ref "RE9") (pin "1") (pinfunction "1_1") (pintype "passive"))
    )
    (net (code "43") (name "Net-(IC2C-OUT)") (class "Default")
      (node (ref "CE1") (pin "1") (pinfunction "1_1") (pintype "passive"))
      (node (ref "IC2") (pin "8") (pinfunction "OUT_8") (pintype "output"))
      (node (ref "RE9") (pin "2") (pinfunction "2_2") (pintype "passive"))
    )
    (net (code "44") (name "Net-(IC2D--IN)") (class "Default")
      (node (ref "IC2") (pin "13") (pinfunction "-IN_13") (pintype "input"))
      (node (ref "RE16") (pin "1") (pinfunction "1_1") (pintype "passive"))
      (node (ref "RE3") (pin "1") (pinfunction "1_1") (pintype "passive"))
      (node (ref "RE5") (pin "2") (pinfunction "2_2") (pintype "passive"))
    )
    (net (code "45") (name "Net-(IC2D-OUT)") (class "Default")
      (node (ref "IC2") (pin "14") (pinfunction "OUT_14") (pintype "output"))
      (node (ref "RE17") (pin "1") (pinfunction "1_1") (pintype "passive"))
    )
    (net (code "46") (name "Net-(IC3A-+IN)") (class "Default")
      (node (ref "CI1") (pin "2") (pinfunction "2_2") (pintype "passive"))
      (node (ref "IC3") (pin "3") (pinfunction "+IN_3") (pintype "input"))
      (node (ref "RI1") (pin "2") (pinfunction "2_2") (pintype "passive"))
    )
    (net (code "47") (name "Net-(IC3A--IN)") (class "Default")
      (node (ref "IC3") (pin "2") (pinfunction "-IN_2") (pintype "input"))
      (node (ref "RI4") (pin "1") (pinfunction "1_1") (pintype "passive"))
      (node (ref "RI5") (pin "2") (pinfunction "2_2") (pintype "passive"))
    )
    (net (code "48") (name "Net-(IC3A-OUT)") (class "Default")
      (node (ref "IC3") (pin "1") (pinfunction "OUT_1") (pintype "output"))
      (node (ref "RI2") (pin "1") (pinfunction "1_1") (pintype "passive"))
      (node (ref "RI4") (pin "2") (pinfunction "2_2") (pintype "passive"))
    )
    (net (code "49") (name "Net-(IC3B-+IN)") (class "Default")
      (node (ref "CI2") (pin "2") (pinfunction "2_2") (pintype "passive"))
      (node (ref "IC3") (pin "5") (pinfunction "+IN_5") (pintype "input"))
      (node (ref "RI34") (pin "2") (pinfunction "2_2") (pintype "passive"))
    )
    (net (code "50") (name "Net-(IC3B--IN)") (class "Default")
      (node (ref "IC3") (pin "6") (pinfunction "-IN_6") (pintype "input"))
      (node (ref "RI5") (pin "1") (pinfunction "1_1") (pintype "passive"))
      (node (ref "RI6") (pin "1") (pinfunction "1_1") (pintype "passive"))
    )
    (net (code "51") (name "Net-(IC3B-OUT)") (class "Default")
      (node (ref "IC3") (pin "7") (pinfunction "OUT_7") (pintype "output"))
      (node (ref "RI6") (pin "2") (pinfunction "2_2") (pintype "passive"))
      (node (ref "RI7") (pin "1") (pinfunction "1_1") (pintype "passive"))
    )
    (net (code "52") (name "Net-(IC3C-+IN)") (class "Default")
      (node (ref "IC3") (pin "10") (pinfunction "+IN_10") (pintype "input"))
      (node (ref "RI7") (pin "2") (pinfunction "2_2") (pintype "passive"))
      (node (ref "RI8") (pin "1") (pinfunction "1_1") (pintype "passive"))
    )
    (net (code "53") (name "Net-(IC3C--IN)") (class "Default")
      (node (ref "IC3") (pin "9") (pinfunction "-IN_9") (pintype "input"))
      (node (ref "RI2") (pin "2") (pinfunction "2_2") (pintype "passive"))
      (node (ref "RI3") (pin "1") (pinfunction "1_1") (pintype "passive"))
    )
    (net (code "54") (name "Net-(IC3C-OUT)") (class "Default")
      (node (ref "IC3") (pin "8") (pinfunction "OUT_8") (pintype "output"))
      (node (ref "RI10") (pin "1") (pinfunction "1_1") (pintype "passive"))
      (node (ref "RI11") (pin "1") (pinfunction "1_1") (pintype "passive"))
      (node (ref "RI3") (pin "2") (pinfunction "2_2") (pintype "passive"))
      (node (ref "RI9") (pin "2") (pinfunction "2_2") (pintype "passive"))
    )
    (net (code "55") (name "Net-(IC3D--IN)") (class "Default")
      (node (ref "CI3") (pin "2") (pinfunction "2_2") (pintype "passive"))
      (node (ref "IC3") (pin "13") (pinfunction "-IN_13") (pintype "input"))
      (node (ref "RI9") (pin "1") (pinfunction "1_1") (pintype "passive"))
    )
    (net (code "56") (name "Net-(IC3D-OUT)") (class "Default")
      (node (ref "CI3") (pin "1") (pinfunction "1_1") (pintype "passive"))
      (node (ref "IC3") (pin "14") (pinfunction "OUT_14") (pintype "output"))
      (node (ref "RI8") (pin "2") (pinfunction "2_2") (pintype "passive"))
    )
    (net (code "57") (name "Net-(IC4A-+IN)") (class "Default")
      (node (ref "IC4") (pin "3") (pinfunction "+IN_3") (pintype "input"))
      (node (ref "RI10") (pin "2") (pinfunction "2_2") (pintype "passive"))
      (node (ref "RI12") (pin "1") (pinfunction "1_1") (pintype "passive"))
    )
    (net (code "58") (name "Net-(IC4C-+IN)") (class "Default")
      (node (ref "CP6") (pin "2") (pinfunction "2_2") (pintype "passive"))
      (node (ref "IC4") (pin "10") (pinfunction "+IN_10") (pintype "input"))
      (node (ref "RP13") (pin "2") (pinfunction "2_2") (pintype "passive"))
    )
    (net (code "59") (name "Net-(IC4C--IN)") (class "Default")
      (node (ref "CP7") (pin "2") (pinfunction "2_2") (pintype "passive"))
      (node (ref "IC4") (pin "9") (pinfunction "-IN_9") (pintype "input"))
      (node (ref "RP14") (pin "2") (pinfunction "2_2") (pintype "passive"))
      (node (ref "RP15") (pin "1") (pinfunction "1_1") (pintype "passive"))
    )
    (net (code "60") (name "Net-(IC4C-OUT)") (class "Default")
      (node (ref "CP7") (pin "1") (pinfunction "1_1") (pintype "passive"))
      (node (ref "IC4") (pin "8") (pinfunction "OUT_8") (pintype "output"))
      (node (ref "RP15") (pin "2") (pinfunction "2_2") (pintype "passive"))
      (node (ref "RP16") (pin "1") (pinfunction "1_1") (pintype "passive"))
    )
    (net (code "61") (name "Net-(IC4D-+IN)") (class "Default")
      (node (ref "CP8") (pin "1") (pinfunction "1_1") (pintype "passive"))
      (node (ref "IC4") (pin "12") (pinfunction "+IN_12") (pintype "input"))
      (node (ref "RP17") (pin "2") (pinfunction "2_2") (pintype "passive"))
    )
    (net (code "62") (name "Net-(IC5A-+IN)") (class "Default")
      (node (ref "CI11") (pin "1") (pinfunction "1_1") (pintype "passive"))
      (node (ref "IC5") (pin "3") (pinfunction "+IN_3") (pintype "input"))
      (node (ref "RI28") (pin "2") (pinfunction "2_2") (pintype "passive"))
    )
    (net (code "63") (name "Net-(IC5A--IN)") (class "Default")
      (node (ref "IC5") (pin "2") (pinfunction "-IN_2") (pintype "input"))
      (node (ref "RI29") (pin "2") (pinfunction "2_2") (pintype "passive"))
      (node (ref "RI30") (pin "1") (pinfunction "1_1") (pintype "passive"))
    )
    (net (code "64") (name "Net-(IC5B-+IN)") (class "Default")
      (node (ref "CI13") (pin "1") (pinfunction "1_1") (pintype "passive"))
      (node (ref "IC5") (pin "5") (pinfunction "+IN_5") (pintype "input"))
      (node (ref "RI31") (pin "2") (pinfunction "2_2") (pintype "passive"))
    )
    (net (code "65") (name "Net-(IC5B--IN)") (class "Default")
      (node (ref "IC5") (pin "6") (pinfunction "-IN_6") (pintype "input"))
      (node (ref "RI32") (pin "1") (pinfunction "1_1") (pintype "passive"))
      (node (ref "RI33") (pin "2") (pinfunction "2_2") (pintype "passive"))
    )
    (net (code "66") (name "Net-(IC5C-+IN)") (class "Default")
      (node (ref "CI8") (pin "2") (pinfunction "2_2") (pintype "passive"))
      (node (ref "IC5") (pin "10") (pinfunction "+IN_10") (pintype "input"))
      (node (ref "RI24") (pin "2") (pinfunction "2_2") (pintype "passive"))
    )
    (net (code "67") (name "Net-(IC5C--IN)") (class "Default")
      (node (ref "CI10") (pin "1") (pinfunction "1_1") (pintype "passive"))
      (node (ref "IC5") (pin "9") (pinfunction "-IN_9") (pintype "input"))
      (node (ref "RI25") (pin "1") (pinfunction "1_1") (pintype "passive"))
      (node (ref "RI26") (pin "2") (pinfunction "2_2") (pintype "passive"))
    )
    (net (code "68") (name "Net-(IC5C-OUT)") (class "Default")
      (node (ref "CI10") (pin "2") (pinfunction "2_2") (pintype "passive"))
      (node (ref "IC5") (pin "8") (pinfunction "OUT_8") (pintype "output"))
      (node (ref "RI25") (pin "2") (pinfunction "2_2") (pintype "passive"))
      (node (ref "RI27") (pin "1") (pinfunction "1_1") (pintype "passive"))
    )
    (net (code "69") (name "Net-(IC5D-+IN)") (class "Default")
      (node (ref "IC5") (pin "12") (pinfunction "+IN_12") (pintype "input"))
      (node (ref "RI17") (pin "2") (pinfunction "2_2") (pintype "passive"))
      (node (ref "RI18") (pin "1") (pinfunction "1_1") (pintype "passive"))
    )
    (net (code "70") (name "Net-(IC5D--IN)") (class "Default")
      (node (ref "IC5") (pin "13") (pinfunction "-IN_13") (pintype "input"))
      (node (ref "RI20") (pin "2") (pinfunction "2_2") (pintype "passive"))
      (node (ref "RI21") (pin "1") (pinfunction "1_1") (pintype "passive"))
    )
    (net (code "71") (name "Net-(IC5D-OUT)") (class "Default")
      (node (ref "IC5") (pin "14") (pinfunction "OUT_14") (pintype "output"))
      (node (ref "RI19") (pin "2") (pinfunction "2_2") (pintype "passive"))
      (node (ref "RI21") (pin "2") (pinfunction "2_2") (pintype "passive"))
    )
    (net (code "72") (name "Net-(IC6A--IN)") (class "Default")
      (node (ref "IC6") (pin "2") (pinfunction "-IN_2") (pintype "input"))
      (node (ref "RP8") (pin "1") (pinfunction "1_1") (pintype "passive"))
      (node (ref "RP9") (pin "2") (pinfunction "2_2") (pintype "passive"))
    )
    (net (code "73") (name "Net-(IC6A-OUT)") (class "Default")
      (node (ref "IC6") (pin "1") (pinfunction "OUT_1") (pintype "output"))
      (node (ref "RP6") (pin "1") (pinfunction "1_1") (pintype "passive"))
      (node (ref "RP8") (pin "2") (pinfunction "2_2") (pintype "passive"))
    )
    (net (code "74") (name "Net-(IC6B--IN)") (class "Default")
      (node (ref "IC6") (pin "6") (pinfunction "-IN_6") (pintype "input"))
      (node (ref "RP10") (pin "1") (pinfunction "1_1") (pintype "passive"))
      (node (ref "RP9") (pin "1") (pinfunction "1_1") (pintype "passive"))
    )
    (net (code "75") (name "Net-(IC6B-OUT)") (class "Default")
      (node (ref "IC6") (pin "7") (pinfunction "OUT_7") (pintype "output"))
      (node (ref "RP10") (pin "2") (pinfunction "2_2") (pintype "passive"))
      (node (ref "RP11") (pin "1") (pinfunction "1_1") (pintype "passive"))
    )
    (net (code "76") (name "Net-(IC6C-+IN)") (class "Default")
      (node (ref "IC6") (pin "10") (pinfunction "+IN_10") (pintype "input"))
      (node (ref "RP11") (pin "2") (pinfunction "2_2") (pintype "passive"))
      (node (ref "RP12") (pin "1") (pinfunction "1_1") (pintype "passive"))
    )
    (net (code "77") (name "Net-(IC6C--IN)") (class "Default")
      (node (ref "IC6") (pin "9") (pinfunction "-IN_9") (pintype "input"))
      (node (ref "RP6") (pin "2") (pinfunction "2_2") (pintype "passive"))
      (node (ref "RP7") (pin "1") (pinfunction "1_1") (pintype "passive"))
    )
    (net (code "78") (name "Net-(IC6C-OUT)") (class "Default")
      (node (ref "CP6") (pin "1") (pinfunction "1_1") (pintype "passive"))
      (node (ref "IC6") (pin "8") (pinfunction "OUT_8") (pintype "output"))
      (node (ref "RP7") (pin "2") (pinfunction "2_2") (pintype "passive"))
    )
    (net (code "79") (name "Net-(IC7A-+IN)") (class "Default")
      (node (ref "CA1") (pin "1") (pinfunction "1_1") (pintype "passive"))
      (node (ref "IC7") (pin "3") (pinfunction "+IN_3") (pintype "input"))
      (node (ref "RA1") (pin "2") (pinfunction "2_2") (pintype "passive"))
      (node (ref "RA2") (pin "2") (pinfunction "2_2") (pintype "passive"))
    )
    (net (code "80") (name "Net-(IC7A--IN)") (class "Default")
      (node (ref "IC7") (pin "2") (pinfunction "-IN_2") (pintype "input"))
      (node (ref "RA3") (pin "2") (pinfunction "2_2") (pintype "passive"))
      (node (ref "RA4") (pin "2") (pinfunction "2_2") (pintype "passive"))
    )
    (net (code "81") (name "Net-(IC7B-+IN)") (class "Default")
      (node (ref "CA2") (pin "1") (pinfunction "1_1") (pintype "passive"))
      (node (ref "IC7") (pin "5") (pinfunction "+IN_5") (pintype "input"))
      (node (ref "RA5") (pin "2") (pinfunction "2_2") (pintype "passive"))
      (node (ref "RA6") (pin "2") (pinfunction "2_2") (pintype "passive"))
    )
    (net (code "82") (name "Net-(IC7B--IN)") (class "Default")
      (node (ref "IC7") (pin "6") (pinfunction "-IN_6") (pintype "input"))
      (node (ref "RA7") (pin "2") (pinfunction "2_2") (pintype "passive"))
      (node (ref "RA8") (pin "2") (pinfunction "2_2") (pintype "passive"))
    )
    (net (code "83") (name "Net-(IC7C-+IN)") (class "Default")
      (node (ref "CA3") (pin "1") (pinfunction "1_1") (pintype "passive"))
      (node (ref "IC7") (pin "10") (pinfunction "+IN_10") (pintype "input"))
      (node (ref "RA10") (pin "2") (pinfunction "2_2") (pintype "passive"))
      (node (ref "RA9") (pin "2") (pinfunction "2_2") (pintype "passive"))
    )
    (net (code "84") (name "Net-(IC7C--IN)") (class "Default")
      (node (ref "IC7") (pin "9") (pinfunction "-IN_9") (pintype "input"))
      (node (ref "RA11") (pin "2") (pinfunction "2_2") (pintype "passive"))
      (node (ref "RA12") (pin "2") (pinfunction "2_2") (pintype "passive"))
    )
    (net (code "85") (name "Net-(IC7D-+IN)") (class "Default")
      (node (ref "CA4") (pin "1") (pinfunction "1_1") (pintype "passive"))
      (node (ref "IC7") (pin "12") (pinfunction "+IN_12") (pintype "input"))
      (node (ref "RA13") (pin "2") (pinfunction "2_2") (pintype "passive"))
      (node (ref "RA14") (pin "2") (pinfunction "2_2") (pintype "passive"))
    )
    (net (code "86") (name "Net-(IC7D--IN)") (class "Default")
      (node (ref "IC7") (pin "13") (pinfunction "-IN_13") (pintype "input"))
      (node (ref "RA15") (pin "2") (pinfunction "2_2") (pintype "passive"))
      (node (ref "RA16") (pin "2") (pinfunction "2_2") (pintype "passive"))
    )
    (net (code "87") (name "Net-(IC8-CV)") (class "Default")
      (node (ref "CP1") (pin "1") (pinfunction "1_1") (pintype "passive"))
      (node (ref "IC8") (pin "5") (pinfunction "CV_5") (pintype "input"))
    )
    (net (code "88") (name "Net-(IC8-DIS)") (class "Default")
      (node (ref "IC8") (pin "7") (pinfunction "DIS_7") (pintype "input"))
      (node (ref "RP1") (pin "1") (pinfunction "1_1") (pintype "passive"))
    )
    (net (code "89") (name "Net-(IC8-Q)") (class "Default")
      (node (ref "IC8") (pin "3") (pinfunction "Q_3") (pintype "output"))
      (node (ref "RP4") (pin "1") (pinfunction "1_1") (pintype "passive"))
    )
    (net (code "90") (name "Net-(IC8-THR)") (class "Default")
      (node (ref "CP2") (pin "2") (pinfunction "2_2") (pintype "passive"))
      (node (ref "IC8") (pin "2") (pinfunction "TR_2") (pintype "input"))
      (node (ref "IC8") (pin "6") (pinfunction "THR_6") (pintype "input"))
      (node (ref "RP1") (pin "2") (pinfunction "2_2") (pintype "passive"))
      (node (ref "RP2") (pin "1") (pinfunction "1_1") (pintype "passive"))
    )
    (net (code "91") (name "Net-(IC9-CV)") (class "Default")
      (node (ref "CI4") (pin "1") (pinfunction "1_1") (pintype "passive"))
      (node (ref "IC9") (pin "5") (pinfunction "CV_5") (pintype "input"))
    )
    (net (code "92") (name "Net-(IC9-DIS)") (class "Default")
      (node (ref "IC9") (pin "7") (pinfunction "DIS_7") (pintype "input"))
      (node (ref "RI15") (pin "1") (pinfunction "1_1") (pintype "passive"))
    )
    (net (code "93") (name "Net-(IC9-Q)") (class "Default")
      (node (ref "CI6") (pin "2") (pinfunction "2_2") (pintype "passive"))
      (node (ref "IC9") (pin "3") (pinfunction "Q_3") (pintype "output"))
    )
    (net (code "94") (name "Net-(IC9-THR)") (class "Default")
      (node (ref "CI5") (pin "2") (pinfunction "2_2") (pintype "passive"))
      (node (ref "IC9") (pin "2") (pinfunction "TR_2") (pintype "input"))
      (node (ref "IC9") (pin "6") (pinfunction "THR_6") (pintype "input"))
      (node (ref "RI14") (pin "1") (pinfunction "1_1") (pintype "passive"))
      (node (ref "RI15") (pin "2") (pinfunction "2_2") (pintype "passive"))
    )
    (net (code "95") (name "Net-(IC10A-A)") (class "Default")
      (node (ref "IC10") (pin "1") (pinfunction "A_1") (pintype "tri_state"))
      (node (ref "RI11") (pin "2") (pinfunction "2_2") (pintype "passive"))
    )
    (net (code "96") (name "Net-(IC10A-B)") (class "Default")
      (node (ref "IC10") (pin "2") (pinfunction "B_2") (pintype "tri_state"))
      (node (ref "IC10") (pin "3") (pinfunction "B_3") (pintype "tri_state"))
      (node (ref "IC4") (pin "2") (pinfunction "-IN_2") (pintype "input"))
    )
    (net (code "97") (name "Net-(IC10B-C)") (class "Default")
      (node (ref "IC10") (pin "5") (pinfunction "C_5") (pintype "input"))
      (node (ref "RI22") (pin "1") (pinfunction "1_1") (pintype "passive"))
      (node (ref "T3") (pin "C") (pinfunction "C_C") (pintype "passive"))
    )
    (net (code "98") (name "Net-(IC10C-A)") (class "Default")
      (node (ref "CP3") (pin "1") (pinfunction "1_1") (pintype "passive"))
      (node (ref "IC10") (pin "11") (pinfunction "A_11") (pintype "tri_state"))
      (node (ref "IC10") (pin "8") (pinfunction "A_8") (pintype "tri_state"))
      (node (ref "IC4") (pin "7") (pinfunction "OUT_7") (pintype "output"))
      (node (ref "RP5") (pin "2") (pinfunction "2_2") (pintype "passive"))
    )
    (net (code "99") (name "Net-(IC10C-C)") (class "Default")
      (node (ref "IC10") (pin "6") (pinfunction "C_6") (pintype "input"))
      (node (ref "RP18") (pin "1") (pinfunction "1_1") (pintype "passive"))
    )
    (net (code "100") (name "Net-(IC10D-C)") (class "Default")
      (node (ref "IC10") (pin "12") (pinfunction "C_12") (pintype "input"))
      (node (ref "R4") (pin "2") (pinfunction "2_2") (pintype "passive"))
    )
    (net (code "101") (name "Net-(RI13-Pad1)") (class "Default")
      (node (ref "RI13") (pin "1") (pinfunction "1_1") (pintype "passive"))
      (node (ref "T3") (pin "B") (pinfunction "B_B") (pintype "passive"))
    )
    (net (code "102") (name "PPG_DP") (class "Default")
      (node (ref "CP3") (pin "2") (pinfunction "2_2") (pintype "passive"))
      (node (ref "IC4") (pin "6") (pinfunction "-IN_6") (pintype "input"))
      (node (ref "J8") (pin "6") (pinfunction "6_6") (pintype "passive"))
      (node (ref "RP5") (pin "1") (pinfunction "1_1") (pintype "passive"))
    )
    (net (code "103") (name "PPG_IAN") (class "Default")
      (node (ref "CP5") (pin "2") (pinfunction "2_2") (pintype "passive"))
      (node (ref "IC10") (pin "10") (pinfunction "B_10") (pintype "tri_state"))
      (node (ref "IC6") (pin "5") (pinfunction "+IN_5") (pintype "input"))
    )
    (net (code "104") (name "PPG_IAP") (class "Default")
      (node (ref "CP4") (pin "2") (pinfunction "2_2") (pintype "passive"))
      (node (ref "IC10") (pin "9") (pinfunction "B_9") (pintype "tri_state"))
      (node (ref "IC6") (pin "3") (pinfunction "+IN_3") (pintype "input"))
    )
    (net (code "105") (name "PPG_LEDN") (class "Default")
      (node (ref "J8") (pin "4") (pinfunction "4_4") (pintype "passive"))
      (node (ref "R4") (pin "1") (pinfunction "1_1") (pintype "passive"))
      (node (ref "T4") (pin "C") (pinfunction "C_C") (pintype "passive"))
    )
    (net (code "106") (name "PPG_LEDP") (class "Default")
      (node (ref "J8") (pin "2") (pinfunction "2_2") (pintype "passive"))
      (node (ref "RP3") (pin "1") (pinfunction "1_1") (pintype "passive"))
    )
    (net (code "107") (name "PPG_OUT") (class "Default")
      (node (ref "CP9") (pin "2") (pinfunction "2_2") (pintype "passive"))
      (node (ref "IC4") (pin "13") (pinfunction "-IN_13") (pintype "input"))
      (node (ref "IC4") (pin "14") (pinfunction "OUT_14") (pintype "output"))
      (node (ref "RA13") (pin "1") (pinfunction "1_1") (pintype "passive"))
    )
    (net (code "108") (name "RESET") (class "Default")
      (node (ref "C19") (pin "+") (pinfunction "+_+") (pintype "passive"))
      (node (ref "J1") (pin "3") (pinfunction "3_3") (pintype "passive"))
    )
    (net (code "109") (name "RESP_OUT") (class "Default")
      (node (ref "IC5") (pin "7") (pinfunction "OUT_7") (pintype "output"))
      (node (ref "RA5") (pin "1") (pinfunction "1_1") (pintype "passive"))
      (node (ref "RI32") (pin "2") (pinfunction "2_2") (pintype "passive"))
    )
    (net (code "110") (name "RX") (class "Default")
      (node (ref "DIGITAL1") (pin "1") (pinfunction "1_1") (pintype "passive"))
      (node (ref "J6") (pin "4") (pinfunction "4_4") (pintype "passive"))
      (node (ref "J7") (pin "4") (pinfunction "4_4") (pintype "passive"))
    )
    (net (code "111") (name "TX") (class "Default")
      (node (ref "DIGITAL1") (pin "2") (pinfunction "2_2") (pintype "passive"))
      (node (ref "J6") (pin "5") (pinfunction "5_5") (pintype "passive"))
      (node (ref "J7") (pin "5") (pinfunction "5_5") (pintype "passive"))
    )
    (net (code "112") (name "VCC_5V") (class "Default")
      (node (ref "IC7") (pin "4") (pinfunction "V+_4") (pintype "power_in"))
      (node (ref "J1") (pin "5") (pinfunction "5_5") (pintype "passive"))
      (node (ref "J6") (pin "3") (pinfunction "3_3") (pintype "passive"))
      (node (ref "J7") (pin "2") (pinfunction "2_2") (pintype "passive"))
    )
    (net (code "113") (name "unconnected-(ANALOG-Pad5)") (class "Default")
      (node (ref "ANALOG") (pin "5") (pinfunction "5_5") (pintype "passive"))
    )
    (net (code "114") (name "unconnected-(ANALOG-Pad6)") (class "Default")
      (node (ref "ANALOG") (pin "6") (pinfunction "6_6") (pintype "passive"))
    )
    (net (code "115") (name "unconnected-(DIGITAL1-Pad3)") (class "Default")
      (node (ref "DIGITAL1") (pin "3") (pinfunction "3_3") (pintype "passive"))
    )
    (net (code "116") (name "unconnected-(DIGITAL1-Pad4)") (class "Default")
      (node (ref "DIGITAL1") (pin "4") (pinfunction "4_4") (pintype "passive"))
    )
    (net (code "117") (name "unconnected-(DIGITAL1-Pad5)") (class "Default")
      (node (ref "DIGITAL1") (pin "5") (pinfunction "5_5") (pintype "passive"))
    )
    (net (code "118") (name "unconnected-(DIGITAL1-Pad6)") (class "Default")
      (node (ref "DIGITAL1") (pin "6") (pinfunction "6_6") (pintype "passive"))
    )
    (net (code "119") (name "unconnected-(DIGITAL1-Pad7)") (class "Default")
      (node (ref "DIGITAL1") (pin "7") (pinfunction "7_7") (pintype "passive"))
    )
    (net (code "120") (name "unconnected-(DIGITAL1-Pad8)") (class "Default")
      (node (ref "DIGITAL1") (pin "8") (pinfunction "8_8") (pintype "passive"))
    )
    (net (code "121") (name "unconnected-(J1-Pad1)") (class "Default")
      (node (ref "J1") (pin "1") (pinfunction "1_1") (pintype "passive"))
    )
    (net (code "122") (name "unconnected-(J1-Pad2)") (class "Default")
      (node (ref "J1") (pin "2") (pinfunction "2_2") (pintype "passive"))
    )
    (net (code "123") (name "unconnected-(J1-Pad4)") (class "Default")
      (node (ref "J1") (pin "4") (pinfunction "4_4") (pintype "passive"))
    )
    (net (code "124") (name "unconnected-(J3-Pad1)") (class "Default")
      (node (ref "J3") (pin "1") (pinfunction "1_1") (pintype "passive"))
    )
    (net (code "125") (name "unconnected-(J3-Pad2)") (class "Default")
      (node (ref "J3") (pin "2") (pinfunction "2_2") (pintype "passive"))
    )
    (net (code "126") (name "unconnected-(J3-Pad3)") (class "Default")
      (node (ref "J3") (pin "3") (pinfunction "3_3") (pintype "passive"))
    )
    (net (code "127") (name "unconnected-(J3-Pad4)") (class "Default")
      (node (ref "J3") (pin "4") (pinfunction "4_4") (pintype "passive"))
    )
    (net (code "128") (name "unconnected-(J3-Pad5)") (class "Default")
      (node (ref "J3") (pin "5") (pinfunction "5_5") (pintype "passive"))
    )
    (net (code "129") (name "unconnected-(J3-Pad6)") (class "Default")
      (node (ref "J3") (pin "6") (pinfunction "6_6") (pintype "passive"))
    )
    (net (code "130") (name "unconnected-(J3-Pad7)") (class "Default")
      (node (ref "J3") (pin "7") (pinfunction "7_7") (pintype "passive"))
    )
    (net (code "131") (name "unconnected-(J3-Pad9)") (class "Default")
      (node (ref "J3") (pin "9") (pinfunction "9_9") (pintype "passive"))
    )
    (net (code "132") (name "unconnected-(J3-Pad10)") (class "Default")
      (node (ref "J3") (pin "10") (pinfunction "10_10") (pintype "passive"))
    )
    (net (code "133") (name "unconnected-(J7-Pad1)") (class "Default")
      (node (ref "J7") (pin "1") (pinfunction "1_1") (pintype "passive"))
    )
    (net (code "134") (name "unconnected-(J7-Pad6)") (class "Default")
      (node (ref "J7") (pin "6") (pinfunction "6_6") (pintype "passive"))
    )
    (net (code "135") (name "unconnected-(J9-PadGNDBREAK)") (class "Default")
      (node (ref "J9") (pin "GNDBREAK") (pinfunction "GNDBREAK_GNDBREAK") (pintype "bidirectional"))
    )
    (net (code "136") (name "unconnected-(J10-PadGNDBREAK)") (class "Default")
      (node (ref "J10") (pin "GNDBREAK") (pinfunction "GNDBREAK_GNDBREAK") (pintype "bidirectional"))
    )
  )
)
